# Equalizer_VUMeter.net
KiCad netlist of a schematic drawn in EAGLE
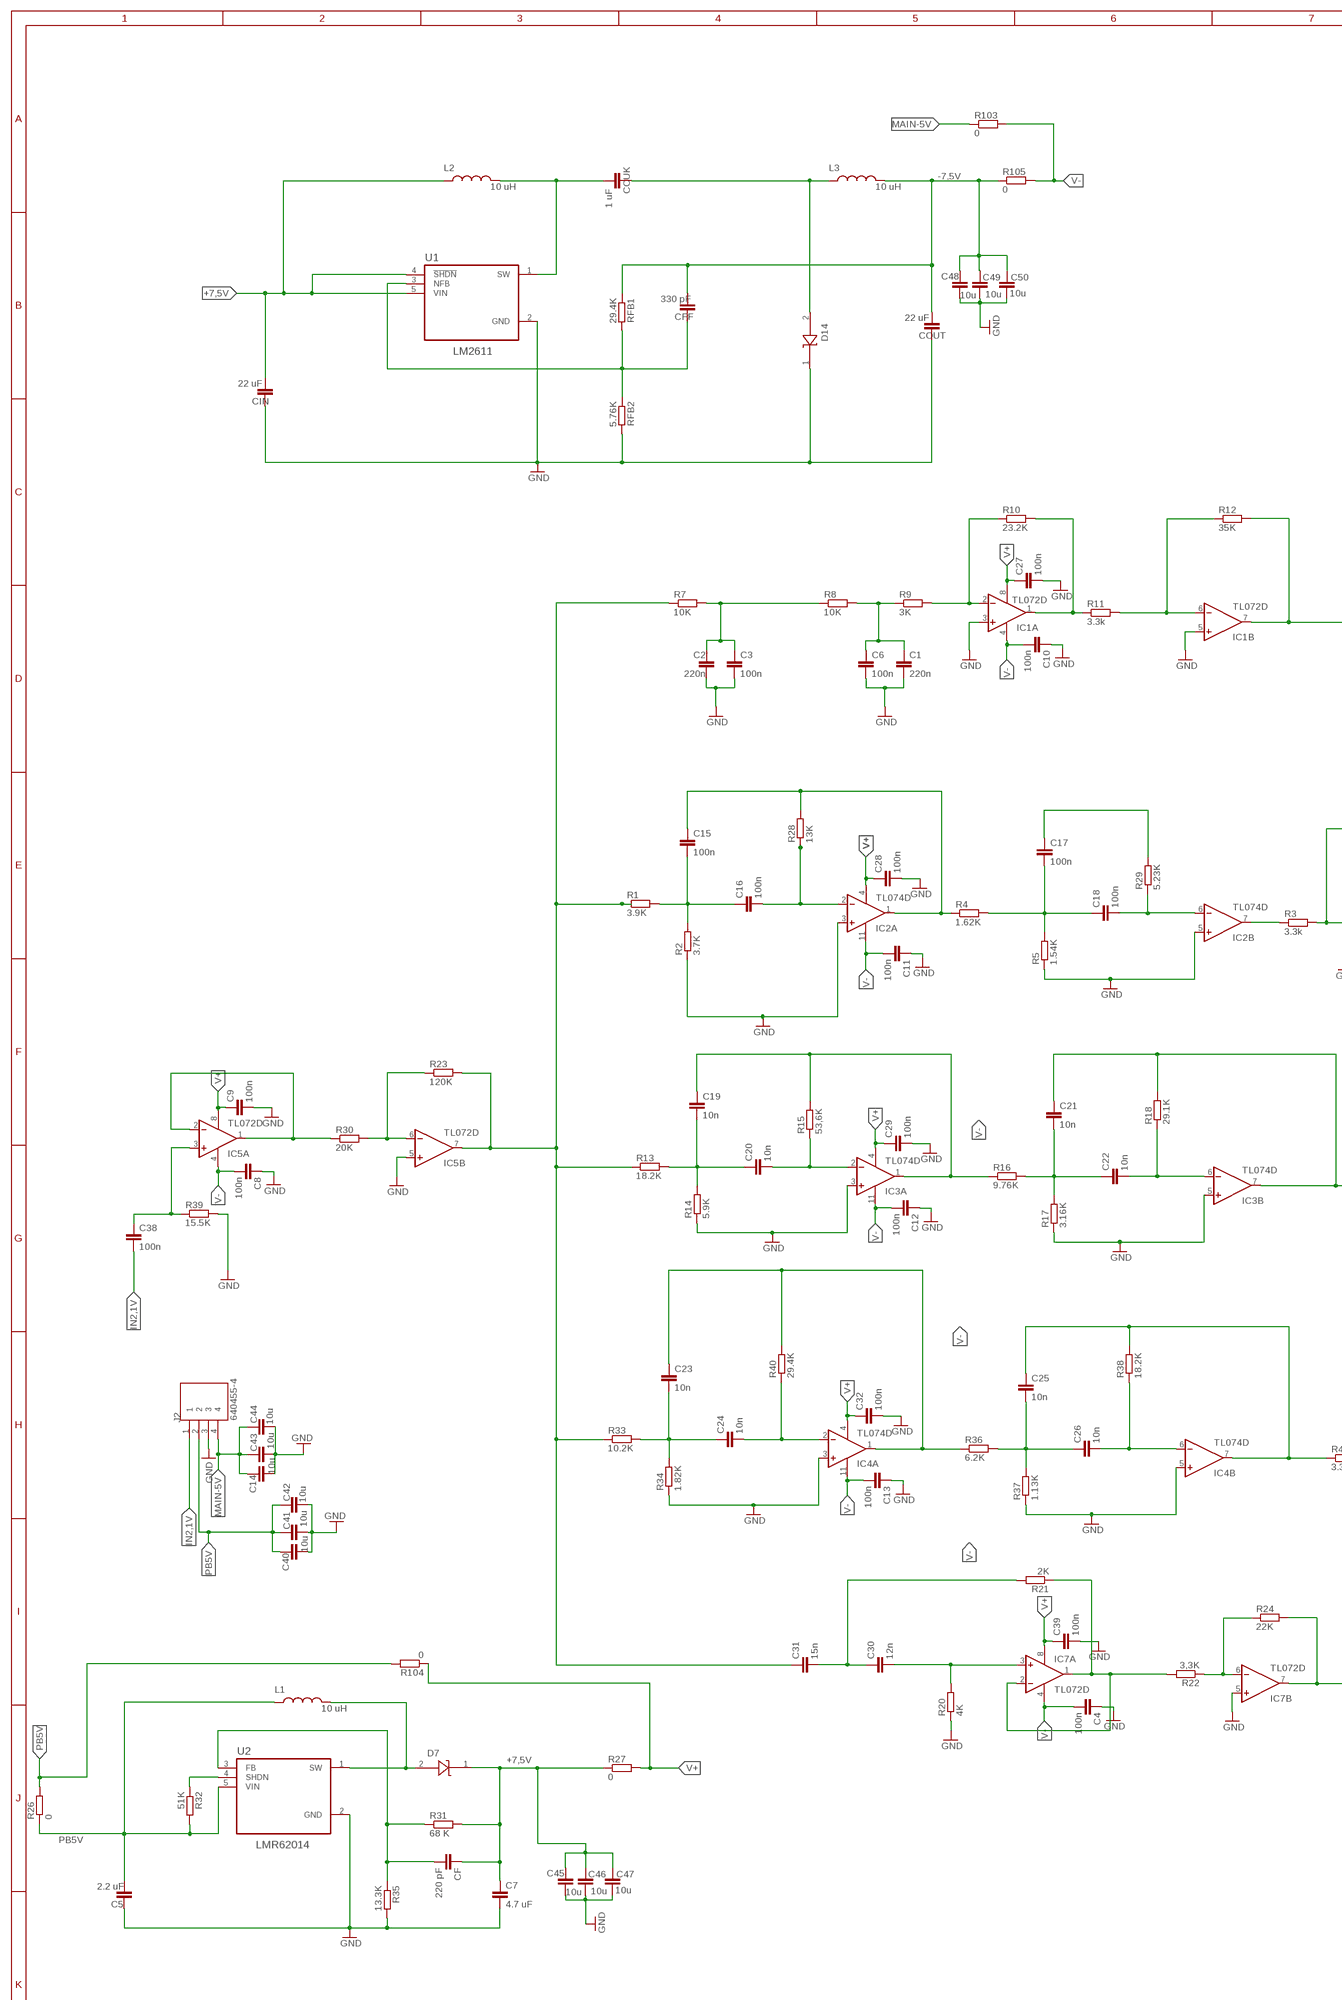
[diagram p0: schematic, sheet 1, part 1 of 3]
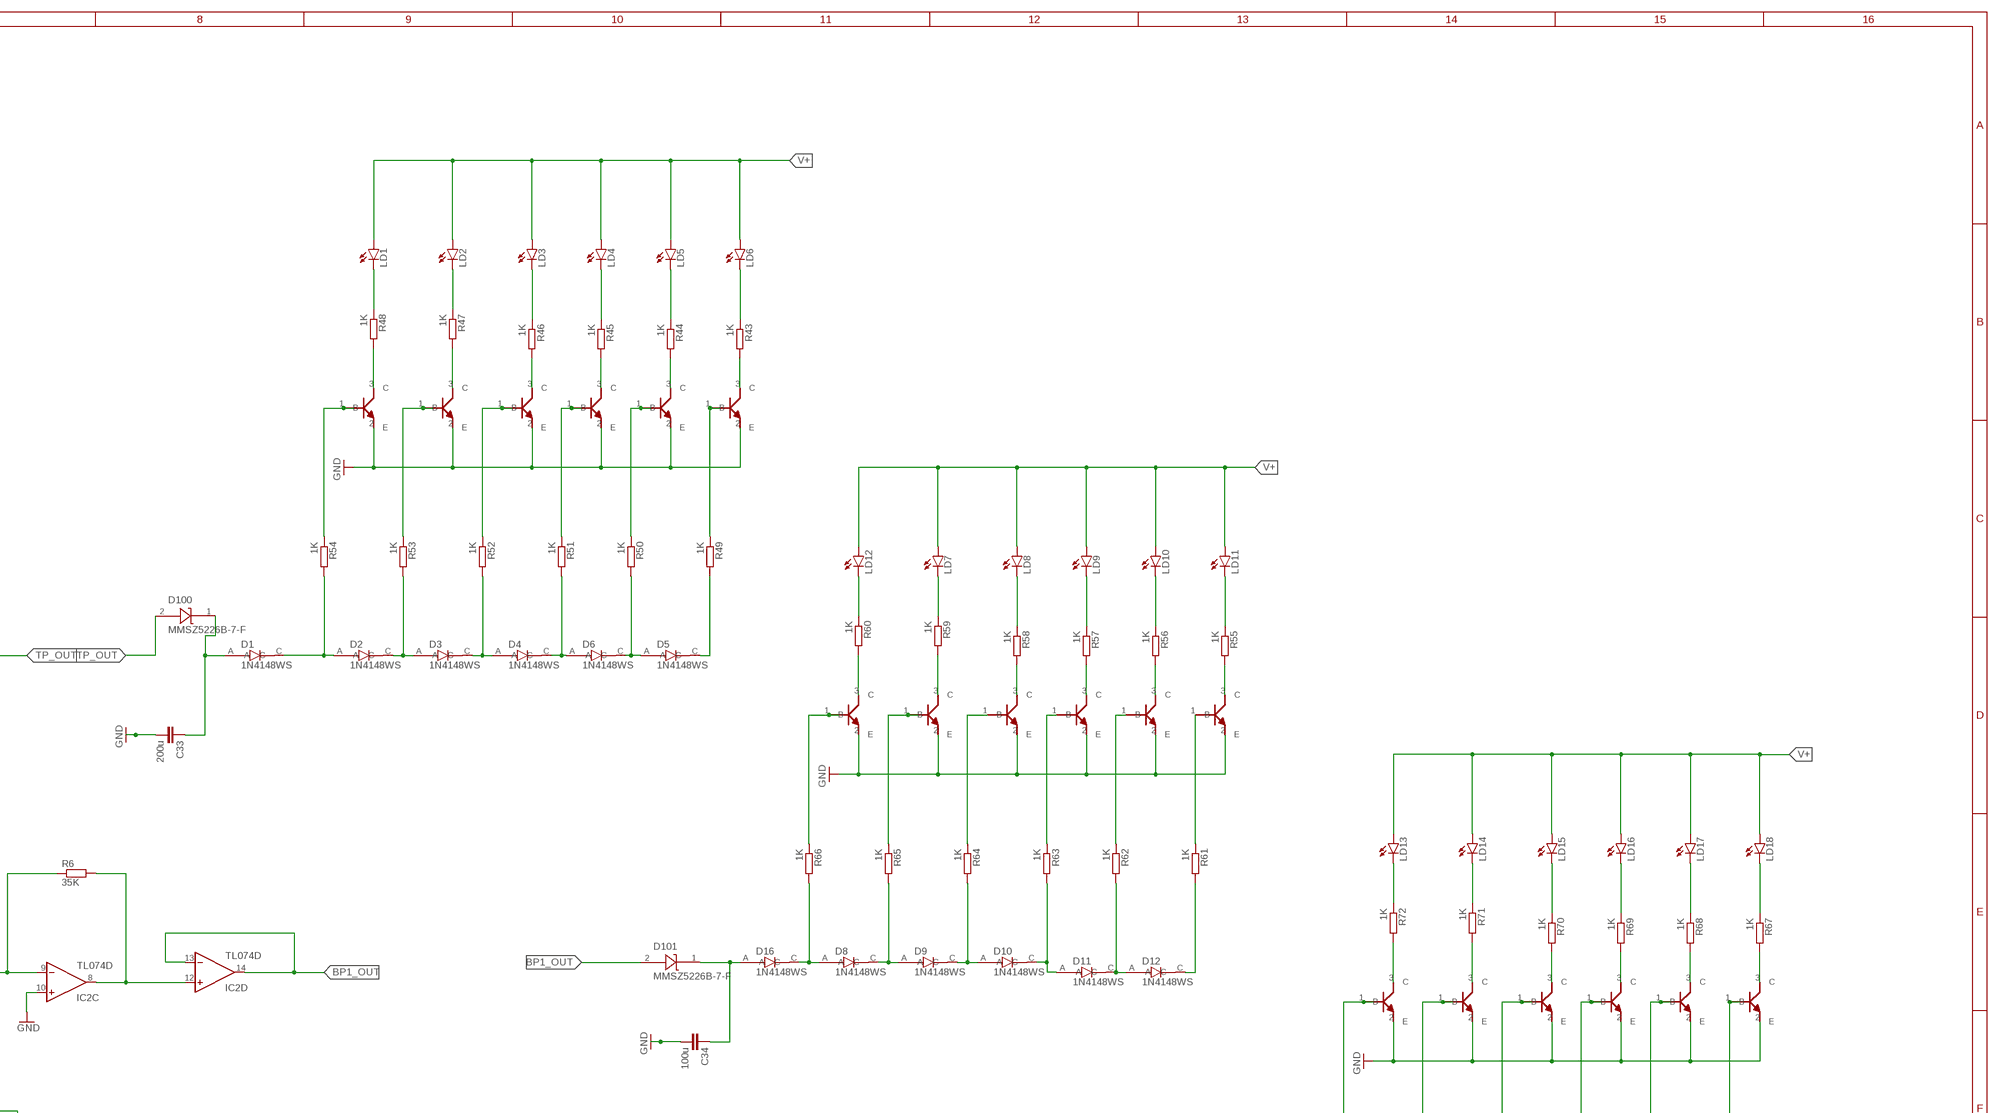
[diagram p1: schematic, sheet 1, part 2 of 3]
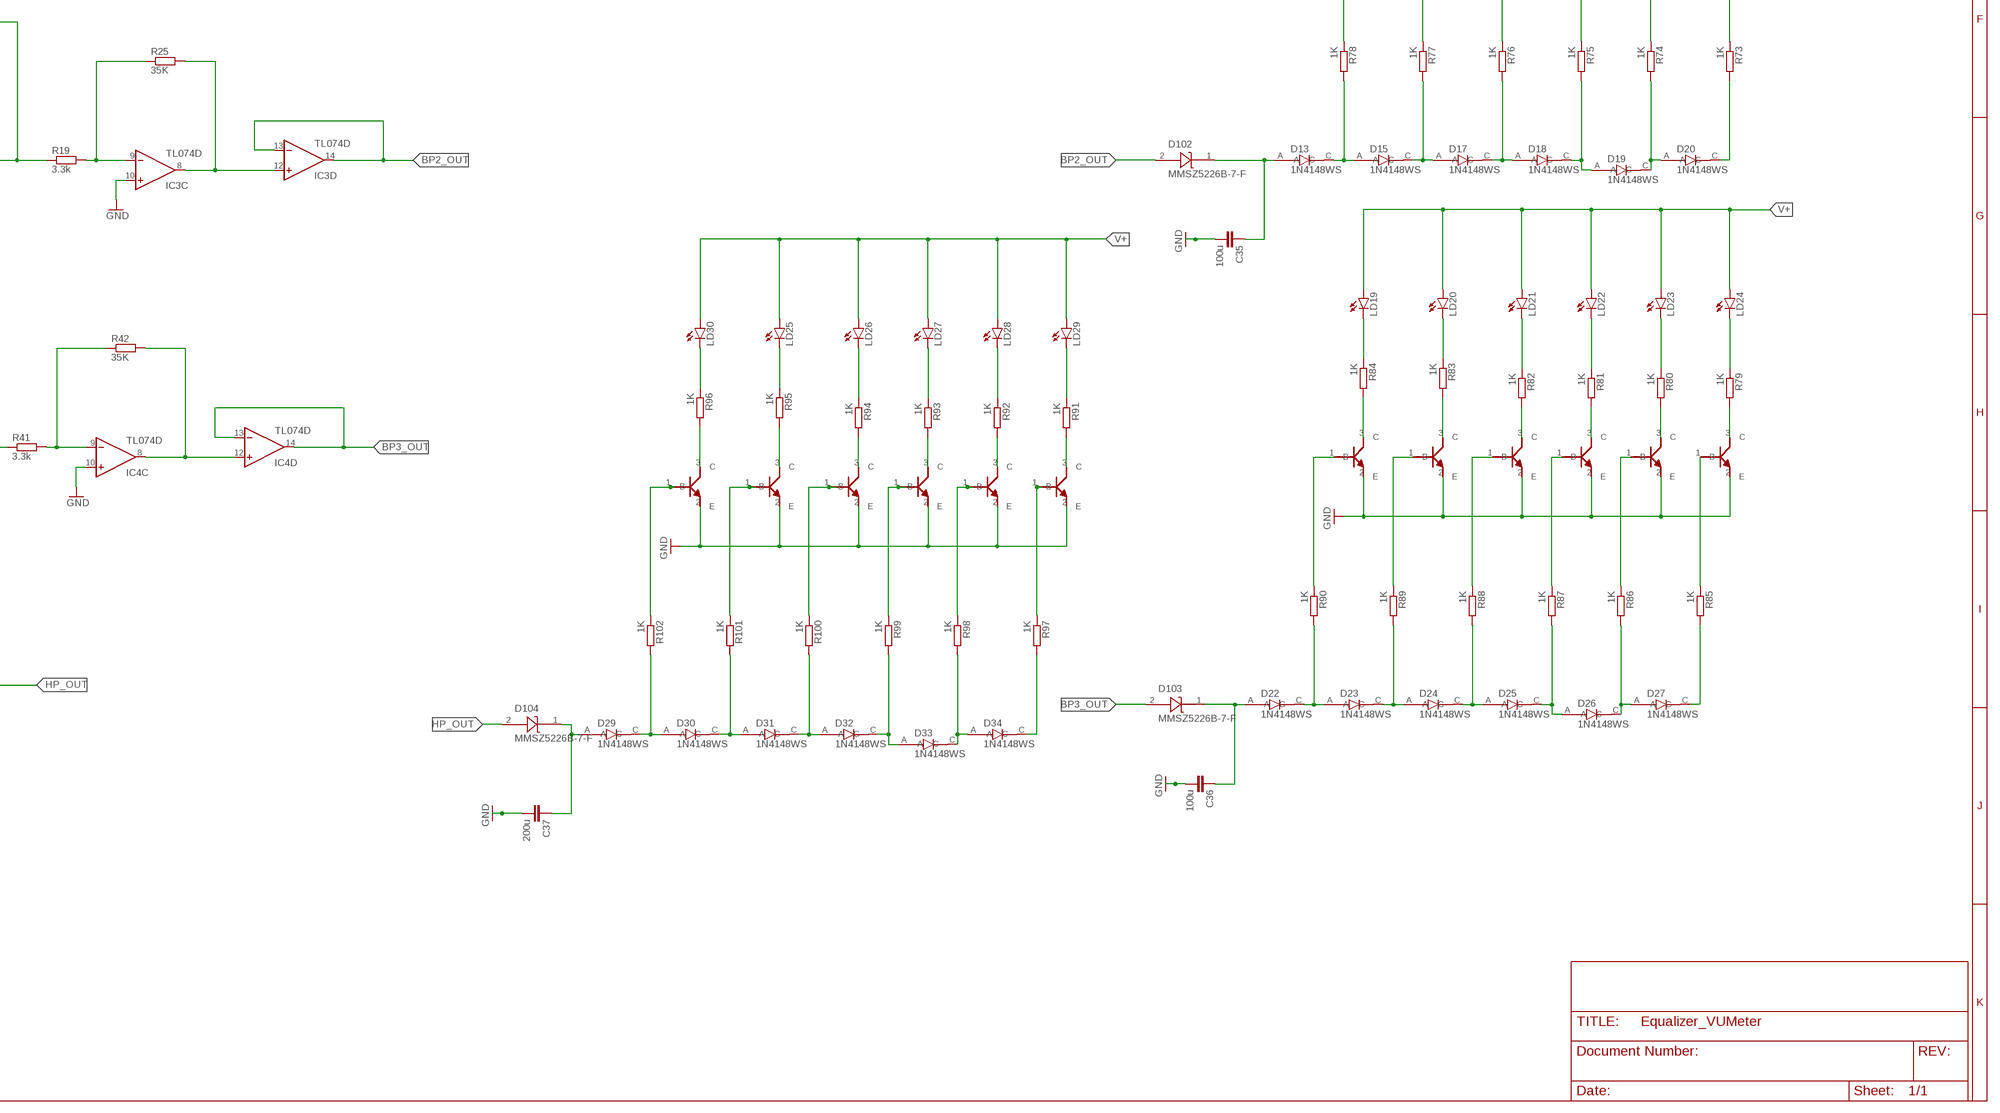
[diagram p2: schematic, sheet 1, part 3 of 3]

(export (version "E")
  (design (tool "Eeschema 10.0.6"))
  (components
    (comp (ref "C1")
      (value "220n")
      (footprint "eagle-import:C0603")
      (libsource (lib "eagle-import") (part "C-EUC0603"))
    )
    (comp (ref "C2")
      (value "220n")
      (footprint "eagle-import:C0603")
      (libsource (lib "eagle-import") (part "C-EUC0603"))
    )
    (comp (ref "C3")
      (value "100n")
      (footprint "eagle-import:C0603")
      (libsource (lib "eagle-import") (part "C-EUC0603"))
    )
    (comp (ref "C4")
      (value "100n")
      (footprint "eagle-import:C0603")
      (libsource (lib "eagle-import") (part "C-EUC0603"))
    )
    (comp (ref "C5")
      (value "2.2 uF")
      (footprint "eagle-import:C0603")
      (libsource (lib "eagle-import") (part "rcl_334_C-EUC0603"))
    )
    (comp (ref "C6")
      (value "100n")
      (footprint "eagle-import:C0603")
      (libsource (lib "eagle-import") (part "C-EUC0603"))
    )
    (comp (ref "C7")
      (value "4.7 uF")
      (footprint "eagle-import:C0603")
      (libsource (lib "eagle-import") (part "rcl_334_C-EUC0603"))
    )
    (comp (ref "C8")
      (value "100n")
      (footprint "eagle-import:C0603")
      (libsource (lib "eagle-import") (part "C-EUC0603"))
    )
    (comp (ref "C9")
      (value "100n")
      (footprint "eagle-import:C0603")
      (libsource (lib "eagle-import") (part "C-EUC0603"))
    )
    (comp (ref "C10")
      (value "100n")
      (footprint "eagle-import:C0603")
      (libsource (lib "eagle-import") (part "C-EUC0603"))
    )
    (comp (ref "C11")
      (value "100n")
      (footprint "eagle-import:C0603")
      (libsource (lib "eagle-import") (part "C-EUC0603"))
    )
    (comp (ref "C12")
      (value "100n")
      (footprint "eagle-import:C0603")
      (libsource (lib "eagle-import") (part "C-EUC0603"))
    )
    (comp (ref "C13")
      (value "100n")
      (footprint "eagle-import:C0603")
      (libsource (lib "eagle-import") (part "C-EUC0603"))
    )
    (comp (ref "C14")
      (value "10u")
      (footprint "eagle-import:C0603")
      (libsource (lib "eagle-import") (part "C-EUC0603"))
    )
    (comp (ref "C15")
      (value "100n")
      (footprint "eagle-import:C0603")
      (libsource (lib "eagle-import") (part "C-EUC0603"))
    )
    (comp (ref "C16")
      (value "100n")
      (footprint "eagle-import:C0603")
      (libsource (lib "eagle-import") (part "C-EUC0603"))
    )
    (comp (ref "C17")
      (value "100n")
      (footprint "eagle-import:C0603")
      (libsource (lib "eagle-import") (part "C-EUC0603"))
    )
    (comp (ref "C18")
      (value "100n")
      (footprint "eagle-import:C0603")
      (libsource (lib "eagle-import") (part "C-EUC0603"))
    )
    (comp (ref "C19")
      (value "10n")
      (footprint "eagle-import:C0603")
      (libsource (lib "eagle-import") (part "C-EUC0603"))
    )
    (comp (ref "C20")
      (value "10n")
      (footprint "eagle-import:C0603")
      (libsource (lib "eagle-import") (part "C-EUC0603"))
    )
    (comp (ref "C21")
      (value "10n")
      (footprint "eagle-import:C0603")
      (libsource (lib "eagle-import") (part "C-EUC0603"))
    )
    (comp (ref "C22")
      (value "10n")
      (footprint "eagle-import:C0603")
      (libsource (lib "eagle-import") (part "C-EUC0603"))
    )
    (comp (ref "C23")
      (value "10n")
      (footprint "eagle-import:C0603")
      (libsource (lib "eagle-import") (part "C-EUC0603"))
    )
    (comp (ref "C24")
      (value "10n")
      (footprint "eagle-import:C0603")
      (libsource (lib "eagle-import") (part "C-EUC0603"))
    )
    (comp (ref "C25")
      (value "10n")
      (footprint "eagle-import:C0603")
      (libsource (lib "eagle-import") (part "C-EUC0603"))
    )
    (comp (ref "C26")
      (value "10n")
      (footprint "eagle-import:C0603")
      (libsource (lib "eagle-import") (part "C-EUC0603"))
    )
    (comp (ref "C27")
      (value "100n")
      (footprint "eagle-import:C0603")
      (libsource (lib "eagle-import") (part "C-EUC0603"))
    )
    (comp (ref "C28")
      (value "100n")
      (footprint "eagle-import:C0603")
      (libsource (lib "eagle-import") (part "C-EUC0603"))
    )
    (comp (ref "C29")
      (value "100n")
      (footprint "eagle-import:C0603")
      (libsource (lib "eagle-import") (part "C-EUC0603"))
    )
    (comp (ref "C30")
      (value "12n")
      (footprint "eagle-import:C0603")
      (libsource (lib "eagle-import") (part "C-EUC0603"))
    )
    (comp (ref "C31")
      (value "15n")
      (footprint "eagle-import:C0603")
      (libsource (lib "eagle-import") (part "C-EUC0603"))
    )
    (comp (ref "C32")
      (value "100n")
      (footprint "eagle-import:C0603")
      (libsource (lib "eagle-import") (part "C-EUC0603"))
    )
    (comp (ref "C33")
      (value "200u")
      (footprint "eagle-import:C0603")
      (libsource (lib "eagle-import") (part "C-EUC0603"))
    )
    (comp (ref "C34")
      (value "100u")
      (footprint "eagle-import:C0603")
      (libsource (lib "eagle-import") (part "C-EUC0603"))
    )
    (comp (ref "C35")
      (value "100u")
      (footprint "eagle-import:C0603")
      (libsource (lib "eagle-import") (part "C-EUC0603"))
    )
    (comp (ref "C36")
      (value "100u")
      (footprint "eagle-import:C0603")
      (libsource (lib "eagle-import") (part "C-EUC0603"))
    )
    (comp (ref "C37")
      (value "200u")
      (footprint "eagle-import:C0603")
      (libsource (lib "eagle-import") (part "C-EUC0603"))
    )
    (comp (ref "C38")
      (value "100n")
      (footprint "eagle-import:C0603")
      (libsource (lib "eagle-import") (part "rcl_334_C-EUC0603"))
    )
    (comp (ref "C39")
      (value "100n")
      (footprint "eagle-import:C0603")
      (libsource (lib "eagle-import") (part "C-EUC0603"))
    )
    (comp (ref "C40")
      (value "10u")
      (footprint "eagle-import:C0603")
      (libsource (lib "eagle-import") (part "C-EUC0603"))
    )
    (comp (ref "C41")
      (value "10u")
      (footprint "eagle-import:C0603")
      (libsource (lib "eagle-import") (part "C-EUC0603"))
    )
    (comp (ref "C42")
      (value "10u")
      (footprint "eagle-import:C0603")
      (libsource (lib "eagle-import") (part "C-EUC0603"))
    )
    (comp (ref "C43")
      (value "10u")
      (footprint "eagle-import:C0603")
      (libsource (lib "eagle-import") (part "C-EUC0603"))
    )
    (comp (ref "C44")
      (value "10u")
      (footprint "eagle-import:C0603")
      (libsource (lib "eagle-import") (part "C-EUC0603"))
    )
    (comp (ref "C45")
      (value "10u")
      (footprint "eagle-import:C0603")
      (libsource (lib "eagle-import") (part "C-EUC0603"))
    )
    (comp (ref "C46")
      (value "10u")
      (footprint "eagle-import:C0603")
      (libsource (lib "eagle-import") (part "C-EUC0603"))
    )
    (comp (ref "C47")
      (value "10u")
      (footprint "eagle-import:C0603")
      (libsource (lib "eagle-import") (part "C-EUC0603"))
    )
    (comp (ref "C48")
      (value "10u")
      (footprint "eagle-import:C0603")
      (libsource (lib "eagle-import") (part "C-EUC0603"))
    )
    (comp (ref "C49")
      (value "10u")
      (footprint "eagle-import:C0603")
      (libsource (lib "eagle-import") (part "C-EUC0603"))
    )
    (comp (ref "C50")
      (value "10u")
      (footprint "eagle-import:C0603")
      (libsource (lib "eagle-import") (part "C-EUC0603"))
    )
    (comp (ref "CCUK")
      (value "1 uF")
      (footprint "eagle-import:C0603")
      (libsource (lib "eagle-import") (part "rcl_334_C-EUC0603"))
    )
    (comp (ref "CF")
      (value "220 pF")
      (footprint "eagle-import:C0603")
      (libsource (lib "eagle-import") (part "rcl_334_C-EUC0603"))
    )
    (comp (ref "CFF")
      (value "330 pF")
      (footprint "eagle-import:C0603")
      (libsource (lib "eagle-import") (part "rcl_334_C-EUC0603"))
    )
    (comp (ref "CIN")
      (value "22 uF")
      (footprint "eagle-import:C0603")
      (libsource (lib "eagle-import") (part "rcl_334_C-EUC0603"))
    )
    (comp (ref "COUT")
      (value "22 uF")
      (footprint "eagle-import:C0603")
      (libsource (lib "eagle-import") (part "rcl_334_C-EUC0603"))
    )
    (comp (ref "D1")
      (value "1N4148WS")
      (footprint "eagle-import:SODFL2512X100N")
      (fields (field (name "MF") "ON Semiconductor"))
      (libsource (lib "eagle-import") (part "1N4148WS"))
    )
    (comp (ref "D2")
      (value "1N4148WS")
      (footprint "eagle-import:SODFL2512X100N")
      (fields (field (name "MF") "ON Semiconductor"))
      (libsource (lib "eagle-import") (part "1N4148WS"))
    )
    (comp (ref "D3")
      (value "1N4148WS")
      (footprint "eagle-import:SODFL2512X100N")
      (fields (field (name "MF") "ON Semiconductor"))
      (libsource (lib "eagle-import") (part "1N4148WS"))
    )
    (comp (ref "D4")
      (value "1N4148WS")
      (footprint "eagle-import:SODFL2512X100N")
      (fields (field (name "MF") "ON Semiconductor"))
      (libsource (lib "eagle-import") (part "1N4148WS"))
    )
    (comp (ref "D5")
      (value "1N4148WS")
      (footprint "eagle-import:SODFL2512X100N")
      (fields (field (name "MF") "ON Semiconductor"))
      (libsource (lib "eagle-import") (part "1N4148WS"))
    )
    (comp (ref "D6")
      (value "1N4148WS")
      (footprint "eagle-import:SODFL2512X100N")
      (fields (field (name "MF") "ON Semiconductor"))
      (libsource (lib "eagle-import") (part "1N4148WS"))
    )
    (comp (ref "D7")
      (value "MMSZ5226B-7-F")
      (footprint "eagle-import:SOD3715X135L32X57N")
      (fields (field (name "MF") "Diodes Inc."))
      (libsource (lib "eagle-import") (part "MMSZ5226B-7-F"))
    )
    (comp (ref "D8")
      (value "1N4148WS")
      (footprint "eagle-import:SODFL2512X100N")
      (fields (field (name "MF") "ON Semiconductor"))
      (libsource (lib "eagle-import") (part "1N4148WS"))
    )
    (comp (ref "D9")
      (value "1N4148WS")
      (footprint "eagle-import:SODFL2512X100N")
      (fields (field (name "MF") "ON Semiconductor"))
      (libsource (lib "eagle-import") (part "1N4148WS"))
    )
    (comp (ref "D10")
      (value "1N4148WS")
      (footprint "eagle-import:SODFL2512X100N")
      (fields (field (name "MF") "ON Semiconductor"))
      (libsource (lib "eagle-import") (part "1N4148WS"))
    )
    (comp (ref "D11")
      (value "1N4148WS")
      (footprint "eagle-import:SODFL2512X100N")
      (fields (field (name "MF") "ON Semiconductor"))
      (libsource (lib "eagle-import") (part "1N4148WS"))
    )
    (comp (ref "D12")
      (value "1N4148WS")
      (footprint "eagle-import:SODFL2512X100N")
      (fields (field (name "MF") "ON Semiconductor"))
      (libsource (lib "eagle-import") (part "1N4148WS"))
    )
    (comp (ref "D13")
      (value "1N4148WS")
      (footprint "eagle-import:SODFL2512X100N")
      (fields (field (name "MF") "ON Semiconductor"))
      (libsource (lib "eagle-import") (part "1N4148WS"))
    )
    (comp (ref "D14")
      (value "MMSZ5226B-7-F")
      (footprint "eagle-import:SOD3715X135L32X57N")
      (fields (field (name "MF") "Diodes Inc."))
      (libsource (lib "eagle-import") (part "MMSZ5226B-7-F"))
    )
    (comp (ref "D15")
      (value "1N4148WS")
      (footprint "eagle-import:SODFL2512X100N")
      (fields (field (name "MF") "ON Semiconductor"))
      (libsource (lib "eagle-import") (part "1N4148WS"))
    )
    (comp (ref "D16")
      (value "1N4148WS")
      (footprint "eagle-import:SODFL2512X100N")
      (fields (field (name "MF") "ON Semiconductor"))
      (libsource (lib "eagle-import") (part "1N4148WS"))
    )
    (comp (ref "D17")
      (value "1N4148WS")
      (footprint "eagle-import:SODFL2512X100N")
      (fields (field (name "MF") "ON Semiconductor"))
      (libsource (lib "eagle-import") (part "1N4148WS"))
    )
    (comp (ref "D18")
      (value "1N4148WS")
      (footprint "eagle-import:SODFL2512X100N")
      (fields (field (name "MF") "ON Semiconductor"))
      (libsource (lib "eagle-import") (part "1N4148WS"))
    )
    (comp (ref "D19")
      (value "1N4148WS")
      (footprint "eagle-import:SODFL2512X100N")
      (fields (field (name "MF") "ON Semiconductor"))
      (libsource (lib "eagle-import") (part "1N4148WS"))
    )
    (comp (ref "D20")
      (value "1N4148WS")
      (footprint "eagle-import:SODFL2512X100N")
      (fields (field (name "MF") "ON Semiconductor"))
      (libsource (lib "eagle-import") (part "1N4148WS"))
    )
    (comp (ref "D22")
      (value "1N4148WS")
      (footprint "eagle-import:SODFL2512X100N")
      (fields (field (name "MF") "ON Semiconductor"))
      (libsource (lib "eagle-import") (part "1N4148WS"))
    )
    (comp (ref "D23")
      (value "1N4148WS")
      (footprint "eagle-import:SODFL2512X100N")
      (fields (field (name "MF") "ON Semiconductor"))
      (libsource (lib "eagle-import") (part "1N4148WS"))
    )
    (comp (ref "D24")
      (value "1N4148WS")
      (footprint "eagle-import:SODFL2512X100N")
      (fields (field (name "MF") "ON Semiconductor"))
      (libsource (lib "eagle-import") (part "1N4148WS"))
    )
    (comp (ref "D25")
      (value "1N4148WS")
      (footprint "eagle-import:SODFL2512X100N")
      (fields (field (name "MF") "ON Semiconductor"))
      (libsource (lib "eagle-import") (part "1N4148WS"))
    )
    (comp (ref "D26")
      (value "1N4148WS")
      (footprint "eagle-import:SODFL2512X100N")
      (fields (field (name "MF") "ON Semiconductor"))
      (libsource (lib "eagle-import") (part "1N4148WS"))
    )
    (comp (ref "D27")
      (value "1N4148WS")
      (footprint "eagle-import:SODFL2512X100N")
      (fields (field (name "MF") "ON Semiconductor"))
      (libsource (lib "eagle-import") (part "1N4148WS"))
    )
    (comp (ref "D29")
      (value "1N4148WS")
      (footprint "eagle-import:SODFL2512X100N")
      (fields (field (name "MF") "ON Semiconductor"))
      (libsource (lib "eagle-import") (part "1N4148WS"))
    )
    (comp (ref "D30")
      (value "1N4148WS")
      (footprint "eagle-import:SODFL2512X100N")
      (fields (field (name "MF") "ON Semiconductor"))
      (libsource (lib "eagle-import") (part "1N4148WS"))
    )
    (comp (ref "D31")
      (value "1N4148WS")
      (footprint "eagle-import:SODFL2512X100N")
      (fields (field (name "MF") "ON Semiconductor"))
      (libsource (lib "eagle-import") (part "1N4148WS"))
    )
    (comp (ref "D32")
      (value "1N4148WS")
      (footprint "eagle-import:SODFL2512X100N")
      (fields (field (name "MF") "ON Semiconductor"))
      (libsource (lib "eagle-import") (part "1N4148WS"))
    )
    (comp (ref "D33")
      (value "1N4148WS")
      (footprint "eagle-import:SODFL2512X100N")
      (fields (field (name "MF") "ON Semiconductor"))
      (libsource (lib "eagle-import") (part "1N4148WS"))
    )
    (comp (ref "D34")
      (value "1N4148WS")
      (footprint "eagle-import:SODFL2512X100N")
      (fields (field (name "MF") "ON Semiconductor"))
      (libsource (lib "eagle-import") (part "1N4148WS"))
    )
    (comp (ref "D100")
      (value "MMSZ5226B-7-F")
      (footprint "eagle-import:SOD3715X135L32X57N")
      (fields (field (name "MF") "Diodes Inc."))
      (libsource (lib "eagle-import") (part "MMSZ5226B-7-F"))
    )
    (comp (ref "D101")
      (value "MMSZ5226B-7-F")
      (footprint "eagle-import:SOD3715X135L32X57N")
      (fields (field (name "MF") "Diodes Inc."))
      (libsource (lib "eagle-import") (part "MMSZ5226B-7-F"))
    )
    (comp (ref "D102")
      (value "MMSZ5226B-7-F")
      (footprint "eagle-import:SOD3715X135L32X57N")
      (fields (field (name "MF") "Diodes Inc."))
      (libsource (lib "eagle-import") (part "MMSZ5226B-7-F"))
    )
    (comp (ref "D103")
      (value "MMSZ5226B-7-F")
      (footprint "eagle-import:SOD3715X135L32X57N")
      (fields (field (name "MF") "Diodes Inc."))
      (libsource (lib "eagle-import") (part "MMSZ5226B-7-F"))
    )
    (comp (ref "D104")
      (value "MMSZ5226B-7-F")
      (footprint "eagle-import:SOD3715X135L32X57N")
      (fields (field (name "MF") "Diodes Inc."))
      (libsource (lib "eagle-import") (part "MMSZ5226B-7-F"))
    )
    (comp (ref "IC1")
      (value "TL072D")
      (footprint "eagle-import:SO08")
      (libsource (lib "eagle-import") (part "TL072D"))
    )
    (comp (ref "IC2")
      (value "TL074D")
      (footprint "eagle-import:SO14")
      (libsource (lib "eagle-import") (part "TL074D"))
    )
    (comp (ref "IC3")
      (value "TL074D")
      (footprint "eagle-import:SO14")
      (libsource (lib "eagle-import") (part "TL074D"))
    )
    (comp (ref "IC4")
      (value "TL074D")
      (footprint "eagle-import:SO14")
      (libsource (lib "eagle-import") (part "TL074D"))
    )
    (comp (ref "IC5")
      (value "TL072D")
      (footprint "eagle-import:SO08")
      (libsource (lib "eagle-import") (part "TL072D"))
    )
    (comp (ref "IC7")
      (value "TL072D")
      (footprint "eagle-import:SO08")
      (libsource (lib "eagle-import") (part "TL072D"))
    )
    (comp (ref "J2")
      (value "640455-4")
      (footprint "eagle-import:TE_640455-4")
      (fields (field (name "MF") "TE Connectivity"))
      (libsource (lib "eagle-import") (part "640455-4"))
    )
    (comp (ref "L1")
      (value "10 uH")
      (footprint "eagle-import:INDC1608X95N")
      (fields (field (name "MF") "Abracon LLC") (field (name "MP") "ASMCI-0603-100M-T"))
      (libsource (lib "eagle-import") (part "ASMCI-0603-100M-T"))
    )
    (comp (ref "L2")
      (value "10 uH")
      (footprint "eagle-import:INDC1608X95N")
      (fields (field (name "MF") "Abracon LLC") (field (name "MP") "ASMCI-0603-100M-T"))
      (libsource (lib "eagle-import") (part "ASMCI-0603-100M-T"))
    )
    (comp (ref "L3")
      (value "10 uH")
      (footprint "eagle-import:INDC1608X95N")
      (fields (field (name "MF") "Abracon LLC") (field (name "MP") "ASMCI-0603-100M-T"))
      (libsource (lib "eagle-import") (part "ASMCI-0603-100M-T"))
    )
    (comp (ref "LD1")
      (value "LEDCHIP-LED0603")
      (footprint "eagle-import:CHIP-LED0603")
      (libsource (lib "eagle-import") (part "LEDCHIP-LED0603"))
    )
    (comp (ref "LD2")
      (value "LEDCHIP-LED0603")
      (footprint "eagle-import:CHIP-LED0603")
      (libsource (lib "eagle-import") (part "LEDCHIP-LED0603"))
    )
    (comp (ref "LD3")
      (value "LEDCHIP-LED0603")
      (footprint "eagle-import:CHIP-LED0603")
      (libsource (lib "eagle-import") (part "LEDCHIP-LED0603"))
    )
    (comp (ref "LD4")
      (value "LEDCHIP-LED0603")
      (footprint "eagle-import:CHIP-LED0603")
      (libsource (lib "eagle-import") (part "LEDCHIP-LED0603"))
    )
    (comp (ref "LD5")
      (value "LEDCHIP-LED0603")
      (footprint "eagle-import:CHIP-LED0603")
      (libsource (lib "eagle-import") (part "LEDCHIP-LED0603"))
    )
    (comp (ref "LD6")
      (value "LEDCHIP-LED0603")
      (footprint "eagle-import:CHIP-LED0603")
      (libsource (lib "eagle-import") (part "LEDCHIP-LED0603"))
    )
    (comp (ref "LD7")
      (value "LEDCHIP-LED0603")
      (footprint "eagle-import:CHIP-LED0603")
      (libsource (lib "eagle-import") (part "LEDCHIP-LED0603"))
    )
    (comp (ref "LD8")
      (value "LEDCHIP-LED0603")
      (footprint "eagle-import:CHIP-LED0603")
      (libsource (lib "eagle-import") (part "LEDCHIP-LED0603"))
    )
    (comp (ref "LD9")
      (value "LEDCHIP-LED0603")
      (footprint "eagle-import:CHIP-LED0603")
      (libsource (lib "eagle-import") (part "LEDCHIP-LED0603"))
    )
    (comp (ref "LD10")
      (value "LEDCHIP-LED0603")
      (footprint "eagle-import:CHIP-LED0603")
      (libsource (lib "eagle-import") (part "LEDCHIP-LED0603"))
    )
    (comp (ref "LD11")
      (value "LEDCHIP-LED0603")
      (footprint "eagle-import:CHIP-LED0603")
      (libsource (lib "eagle-import") (part "LEDCHIP-LED0603"))
    )
    (comp (ref "LD12")
      (value "LEDCHIP-LED0603")
      (footprint "eagle-import:CHIP-LED0603")
      (libsource (lib "eagle-import") (part "LEDCHIP-LED0603"))
    )
    (comp (ref "LD13")
      (value "LEDCHIP-LED0603")
      (footprint "eagle-import:CHIP-LED0603")
      (libsource (lib "eagle-import") (part "LEDCHIP-LED0603"))
    )
    (comp (ref "LD14")
      (value "LEDCHIP-LED0603")
      (footprint "eagle-import:CHIP-LED0603")
      (libsource (lib "eagle-import") (part "LEDCHIP-LED0603"))
    )
    (comp (ref "LD15")
      (value "LEDCHIP-LED0603")
      (footprint "eagle-import:CHIP-LED0603")
      (libsource (lib "eagle-import") (part "LEDCHIP-LED0603"))
    )
    (comp (ref "LD16")
      (value "LEDCHIP-LED0603")
      (footprint "eagle-import:CHIP-LED0603")
      (libsource (lib "eagle-import") (part "LEDCHIP-LED0603"))
    )
    (comp (ref "LD17")
      (value "LEDCHIP-LED0603")
      (footprint "eagle-import:CHIP-LED0603")
      (libsource (lib "eagle-import") (part "LEDCHIP-LED0603"))
    )
    (comp (ref "LD18")
      (value "LEDCHIP-LED0603")
      (footprint "eagle-import:CHIP-LED0603")
      (libsource (lib "eagle-import") (part "LEDCHIP-LED0603"))
    )
    (comp (ref "LD19")
      (value "LEDCHIP-LED0603")
      (footprint "eagle-import:CHIP-LED0603")
      (libsource (lib "eagle-import") (part "LEDCHIP-LED0603"))
    )
    (comp (ref "LD20")
      (value "LEDCHIP-LED0603")
      (footprint "eagle-import:CHIP-LED0603")
      (libsource (lib "eagle-import") (part "LEDCHIP-LED0603"))
    )
    (comp (ref "LD21")
      (value "LEDCHIP-LED0603")
      (footprint "eagle-import:CHIP-LED0603")
      (libsource (lib "eagle-import") (part "LEDCHIP-LED0603"))
    )
    (comp (ref "LD22")
      (value "LEDCHIP-LED0603")
      (footprint "eagle-import:CHIP-LED0603")
      (libsource (lib "eagle-import") (part "LEDCHIP-LED0603"))
    )
    (comp (ref "LD23")
      (value "LEDCHIP-LED0603")
      (footprint "eagle-import:CHIP-LED0603")
      (libsource (lib "eagle-import") (part "LEDCHIP-LED0603"))
    )
    (comp (ref "LD24")
      (value "LEDCHIP-LED0603")
      (footprint "eagle-import:CHIP-LED0603")
      (libsource (lib "eagle-import") (part "LEDCHIP-LED0603"))
    )
    (comp (ref "LD25")
      (value "LEDCHIP-LED0603")
      (footprint "eagle-import:CHIP-LED0603")
      (libsource (lib "eagle-import") (part "LEDCHIP-LED0603"))
    )
    (comp (ref "LD26")
      (value "LEDCHIP-LED0603")
      (footprint "eagle-import:CHIP-LED0603")
      (libsource (lib "eagle-import") (part "LEDCHIP-LED0603"))
    )
    (comp (ref "LD27")
      (value "LEDCHIP-LED0603")
      (footprint "eagle-import:CHIP-LED0603")
      (libsource (lib "eagle-import") (part "LEDCHIP-LED0603"))
    )
    (comp (ref "LD28")
      (value "LEDCHIP-LED0603")
      (footprint "eagle-import:CHIP-LED0603")
      (libsource (lib "eagle-import") (part "LEDCHIP-LED0603"))
    )
    (comp (ref "LD29")
      (value "LEDCHIP-LED0603")
      (footprint "eagle-import:CHIP-LED0603")
      (libsource (lib "eagle-import") (part "LEDCHIP-LED0603"))
    )
    (comp (ref "LD30")
      (value "LEDCHIP-LED0603")
      (footprint "eagle-import:CHIP-LED0603")
      (libsource (lib "eagle-import") (part "LEDCHIP-LED0603"))
    )
    (comp (ref "R1")
      (value "3.9K")
      (footprint "eagle-import:R0603")
      (libsource (lib "eagle-import") (part "R-EU_R0603"))
    )
    (comp (ref "R2")
      (value "3.7K")
      (footprint "eagle-import:R0603")
      (libsource (lib "eagle-import") (part "R-EU_R0603"))
    )
    (comp (ref "R3")
      (value "3.3k")
      (footprint "eagle-import:R0603")
      (libsource (lib "eagle-import") (part "R-EU_R0603"))
    )
    (comp (ref "R4")
      (value "1.62K")
      (footprint "eagle-import:R0603")
      (libsource (lib "eagle-import") (part "R-EU_R0603"))
    )
    (comp (ref "R5")
      (value "1.54K")
      (footprint "eagle-import:R0603")
      (libsource (lib "eagle-import") (part "R-EU_R0603"))
    )
    (comp (ref "R6")
      (value "35K")
      (footprint "eagle-import:R0603")
      (libsource (lib "eagle-import") (part "R-EU_R0603"))
    )
    (comp (ref "R7")
      (value "10K")
      (footprint "eagle-import:R0603")
      (libsource (lib "eagle-import") (part "R-EU_R0603"))
    )
    (comp (ref "R8")
      (value "10K")
      (footprint "eagle-import:R0603")
      (libsource (lib "eagle-import") (part "R-EU_R0603"))
    )
    (comp (ref "R9")
      (value "3K")
      (footprint "eagle-import:R0603")
      (libsource (lib "eagle-import") (part "R-EU_R0603"))
    )
    (comp (ref "R10")
      (value "23.2K")
      (footprint "eagle-import:R0603")
      (libsource (lib "eagle-import") (part "R-EU_R0603"))
    )
    (comp (ref "R11")
      (value "3.3k")
      (footprint "eagle-import:R0603")
      (libsource (lib "eagle-import") (part "R-EU_R0603"))
    )
    (comp (ref "R12")
      (value "35K")
      (footprint "eagle-import:R0603")
      (libsource (lib "eagle-import") (part "R-EU_R0603"))
    )
    (comp (ref "R13")
      (value "18.2K")
      (footprint "eagle-import:R0603")
      (libsource (lib "eagle-import") (part "R-EU_R0603"))
    )
    (comp (ref "R14")
      (value "5.9K")
      (footprint "eagle-import:R0603")
      (libsource (lib "eagle-import") (part "R-EU_R0603"))
    )
    (comp (ref "R15")
      (value "53,6K")
      (footprint "eagle-import:R0603")
      (libsource (lib "eagle-import") (part "R-EU_R0603"))
    )
    (comp (ref "R16")
      (value "9.76K")
      (footprint "eagle-import:R0603")
      (libsource (lib "eagle-import") (part "R-EU_R0603"))
    )
    (comp (ref "R17")
      (value "3.16K")
      (footprint "eagle-import:R0603")
      (libsource (lib "eagle-import") (part "R-EU_R0603"))
    )
    (comp (ref "R18")
      (value "29.1K")
      (footprint "eagle-import:R0603")
      (libsource (lib "eagle-import") (part "R-EU_R0603"))
    )
    (comp (ref "R19")
      (value "3.3k")
      (footprint "eagle-import:R0603")
      (libsource (lib "eagle-import") (part "R-EU_R0603"))
    )
    (comp (ref "R20")
      (value "4K")
      (footprint "eagle-import:R0603")
      (libsource (lib "eagle-import") (part "R-EU_R0603"))
    )
    (comp (ref "R21")
      (value "2K")
      (footprint "eagle-import:R0603")
      (libsource (lib "eagle-import") (part "R-EU_R0603"))
    )
    (comp (ref "R22")
      (value "3,3K")
      (footprint "eagle-import:R0603")
      (libsource (lib "eagle-import") (part "R-EU_R0603"))
    )
    (comp (ref "R23")
      (value "120K")
      (footprint "eagle-import:R0603")
      (libsource (lib "eagle-import") (part "R-EU_R0603"))
    )
    (comp (ref "R24")
      (value "22K")
      (footprint "eagle-import:R0603")
      (libsource (lib "eagle-import") (part "R-EU_R0603"))
    )
    (comp (ref "R25")
      (value "35K")
      (footprint "eagle-import:R0603")
      (libsource (lib "eagle-import") (part "R-EU_R0603"))
    )
    (comp (ref "R26")
      (value "0")
      (footprint "eagle-import:R0603")
      (libsource (lib "eagle-import") (part "R-EU_R0603"))
    )
    (comp (ref "R27")
      (value "0")
      (footprint "eagle-import:R0603")
      (libsource (lib "eagle-import") (part "R-EU_R0603"))
    )
    (comp (ref "R28")
      (value "13K")
      (footprint "eagle-import:R0603")
      (libsource (lib "eagle-import") (part "R-EU_R0603"))
    )
    (comp (ref "R29")
      (value "5.23K")
      (footprint "eagle-import:R0603")
      (libsource (lib "eagle-import") (part "R-EU_R0603"))
    )
    (comp (ref "R30")
      (value "20K")
      (footprint "eagle-import:R0603")
      (libsource (lib "eagle-import") (part "R-EU_R0603"))
    )
    (comp (ref "R31")
      (value "68 K")
      (footprint "eagle-import:R0603")
      (libsource (lib "eagle-import") (part "R-EU_R0603"))
    )
    (comp (ref "R32")
      (value "51K")
      (footprint "eagle-import:R0603")
      (libsource (lib "eagle-import") (part "R-EU_R0603"))
    )
    (comp (ref "R33")
      (value "10.2K")
      (footprint "eagle-import:R0603")
      (libsource (lib "eagle-import") (part "R-EU_R0603"))
    )
    (comp (ref "R34")
      (value "1.82K")
      (footprint "eagle-import:R0603")
      (libsource (lib "eagle-import") (part "R-EU_R0603"))
    )
    (comp (ref "R35")
      (value "13.3K")
      (footprint "eagle-import:R0603")
      (libsource (lib "eagle-import") (part "R-EU_R0603"))
    )
    (comp (ref "R36")
      (value "6.2K")
      (footprint "eagle-import:R0603")
      (libsource (lib "eagle-import") (part "R-EU_R0603"))
    )
    (comp (ref "R37")
      (value "1.13K")
      (footprint "eagle-import:R0603")
      (libsource (lib "eagle-import") (part "R-EU_R0603"))
    )
    (comp (ref "R38")
      (value "18.2K")
      (footprint "eagle-import:R0603")
      (libsource (lib "eagle-import") (part "R-EU_R0603"))
    )
    (comp (ref "R39")
      (value "15.5K")
      (footprint "eagle-import:R0603")
      (libsource (lib "eagle-import") (part "R-EU_R0603"))
    )
    (comp (ref "R40")
      (value "29.4K")
      (footprint "eagle-import:R0603")
      (libsource (lib "eagle-import") (part "R-EU_R0603"))
    )
    (comp (ref "R41")
      (value "3.3k")
      (footprint "eagle-import:R0603")
      (libsource (lib "eagle-import") (part "R-EU_R0603"))
    )
    (comp (ref "R42")
      (value "35K")
      (footprint "eagle-import:R0603")
      (libsource (lib "eagle-import") (part "R-EU_R0603"))
    )
    (comp (ref "R43")
      (value "1K")
      (footprint "eagle-import:R0603")
      (libsource (lib "eagle-import") (part "R-EU_R0603"))
    )
    (comp (ref "R44")
      (value "1K")
      (footprint "eagle-import:R0603")
      (libsource (lib "eagle-import") (part "R-EU_R0603"))
    )
    (comp (ref "R45")
      (value "1K")
      (footprint "eagle-import:R0603")
      (libsource (lib "eagle-import") (part "R-EU_R0603"))
    )
    (comp (ref "R46")
      (value "1K")
      (footprint "eagle-import:R0603")
      (libsource (lib "eagle-import") (part "R-EU_R0603"))
    )
    (comp (ref "R47")
      (value "1K")
      (footprint "eagle-import:R0603")
      (libsource (lib "eagle-import") (part "R-EU_R0603"))
    )
    (comp (ref "R48")
      (value "1K")
      (footprint "eagle-import:R0603")
      (libsource (lib "eagle-import") (part "R-EU_R0603"))
    )
    (comp (ref "R49")
      (value "1K")
      (footprint "eagle-import:R0603")
      (libsource (lib "eagle-import") (part "R-EU_R0603"))
    )
    (comp (ref "R50")
      (value "1K")
      (footprint "eagle-import:R0603")
      (libsource (lib "eagle-import") (part "R-EU_R0603"))
    )
    (comp (ref "R51")
      (value "1K")
      (footprint "eagle-import:R0603")
      (libsource (lib "eagle-import") (part "R-EU_R0603"))
    )
    (comp (ref "R52")
      (value "1K")
      (footprint "eagle-import:R0603")
      (libsource (lib "eagle-import") (part "R-EU_R0603"))
    )
    (comp (ref "R53")
      (value "1K")
      (footprint "eagle-import:R0603")
      (libsource (lib "eagle-import") (part "R-EU_R0603"))
    )
    (comp (ref "R54")
      (value "1K")
      (footprint "eagle-import:R0603")
      (libsource (lib "eagle-import") (part "R-EU_R0603"))
    )
    (comp (ref "R55")
      (value "1K")
      (footprint "eagle-import:R0603")
      (libsource (lib "eagle-import") (part "R-EU_R0603"))
    )
    (comp (ref "R56")
      (value "1K")
      (footprint "eagle-import:R0603")
      (libsource (lib "eagle-import") (part "R-EU_R0603"))
    )
    (comp (ref "R57")
      (value "1K")
      (footprint "eagle-import:R0603")
      (libsource (lib "eagle-import") (part "R-EU_R0603"))
    )
    (comp (ref "R58")
      (value "1K")
      (footprint "eagle-import:R0603")
      (libsource (lib "eagle-import") (part "R-EU_R0603"))
    )
    (comp (ref "R59")
      (value "1K")
      (footprint "eagle-import:R0603")
      (libsource (lib "eagle-import") (part "R-EU_R0603"))
    )
    (comp (ref "R60")
      (value "1K")
      (footprint "eagle-import:R0603")
      (libsource (lib "eagle-import") (part "R-EU_R0603"))
    )
    (comp (ref "R61")
      (value "1K")
      (footprint "eagle-import:R0603")
      (libsource (lib "eagle-import") (part "R-EU_R0603"))
    )
    (comp (ref "R62")
      (value "1K")
      (footprint "eagle-import:R0603")
      (libsource (lib "eagle-import") (part "R-EU_R0603"))
    )
    (comp (ref "R63")
      (value "1K")
      (footprint "eagle-import:R0603")
      (libsource (lib "eagle-import") (part "R-EU_R0603"))
    )
    (comp (ref "R64")
      (value "1K")
      (footprint "eagle-import:R0603")
      (libsource (lib "eagle-import") (part "R-EU_R0603"))
    )
    (comp (ref "R65")
      (value "1K")
      (footprint "eagle-import:R0603")
      (libsource (lib "eagle-import") (part "R-EU_R0603"))
    )
    (comp (ref "R66")
      (value "1K")
      (footprint "eagle-import:R0603")
      (libsource (lib "eagle-import") (part "R-EU_R0603"))
    )
    (comp (ref "R67")
      (value "1K")
      (footprint "eagle-import:R0603")
      (libsource (lib "eagle-import") (part "R-EU_R0603"))
    )
    (comp (ref "R68")
      (value "1K")
      (footprint "eagle-import:R0603")
      (libsource (lib "eagle-import") (part "R-EU_R0603"))
    )
    (comp (ref "R69")
      (value "1K")
      (footprint "eagle-import:R0603")
      (libsource (lib "eagle-import") (part "R-EU_R0603"))
    )
    (comp (ref "R70")
      (value "1K")
      (footprint "eagle-import:R0603")
      (libsource (lib "eagle-import") (part "R-EU_R0603"))
    )
    (comp (ref "R71")
      (value "1K")
      (footprint "eagle-import:R0603")
      (libsource (lib "eagle-import") (part "R-EU_R0603"))
    )
    (comp (ref "R72")
      (value "1K")
      (footprint "eagle-import:R0603")
      (libsource (lib "eagle-import") (part "R-EU_R0603"))
    )
    (comp (ref "R73")
      (value "1K")
      (footprint "eagle-import:R0603")
      (libsource (lib "eagle-import") (part "R-EU_R0603"))
    )
    (comp (ref "R74")
      (value "1K")
      (footprint "eagle-import:R0603")
      (libsource (lib "eagle-import") (part "R-EU_R0603"))
    )
    (comp (ref "R75")
      (value "1K")
      (footprint "eagle-import:R0603")
      (libsource (lib "eagle-import") (part "R-EU_R0603"))
    )
    (comp (ref "R76")
      (value "1K")
      (footprint "eagle-import:R0603")
      (libsource (lib "eagle-import") (part "R-EU_R0603"))
    )
    (comp (ref "R77")
      (value "1K")
      (footprint "eagle-import:R0603")
      (libsource (lib "eagle-import") (part "R-EU_R0603"))
    )
    (comp (ref "R78")
      (value "1K")
      (footprint "eagle-import:R0603")
      (libsource (lib "eagle-import") (part "R-EU_R0603"))
    )
    (comp (ref "R79")
      (value "1K")
      (footprint "eagle-import:R0603")
      (libsource (lib "eagle-import") (part "R-EU_R0603"))
    )
    (comp (ref "R80")
      (value "1K")
      (footprint "eagle-import:R0603")
      (libsource (lib "eagle-import") (part "R-EU_R0603"))
    )
    (comp (ref "R81")
      (value "1K")
      (footprint "eagle-import:R0603")
      (libsource (lib "eagle-import") (part "R-EU_R0603"))
    )
    (comp (ref "R82")
      (value "1K")
      (footprint "eagle-import:R0603")
      (libsource (lib "eagle-import") (part "R-EU_R0603"))
    )
    (comp (ref "R83")
      (value "1K")
      (footprint "eagle-import:R0603")
      (libsource (lib "eagle-import") (part "R-EU_R0603"))
    )
    (comp (ref "R84")
      (value "1K")
      (footprint "eagle-import:R0603")
      (libsource (lib "eagle-import") (part "R-EU_R0603"))
    )
    (comp (ref "R85")
      (value "1K")
      (footprint "eagle-import:R0603")
      (libsource (lib "eagle-import") (part "R-EU_R0603"))
    )
    (comp (ref "R86")
      (value "1K")
      (footprint "eagle-import:R0603")
      (libsource (lib "eagle-import") (part "R-EU_R0603"))
    )
    (comp (ref "R87")
      (value "1K")
      (footprint "eagle-import:R0603")
      (libsource (lib "eagle-import") (part "R-EU_R0603"))
    )
    (comp (ref "R88")
      (value "1K")
      (footprint "eagle-import:R0603")
      (libsource (lib "eagle-import") (part "R-EU_R0603"))
    )
    (comp (ref "R89")
      (value "1K")
      (footprint "eagle-import:R0603")
      (libsource (lib "eagle-import") (part "R-EU_R0603"))
    )
    (comp (ref "R90")
      (value "1K")
      (footprint "eagle-import:R0603")
      (libsource (lib "eagle-import") (part "R-EU_R0603"))
    )
    (comp (ref "R91")
      (value "1K")
      (footprint "eagle-import:R0603")
      (libsource (lib "eagle-import") (part "R-EU_R0603"))
    )
    (comp (ref "R92")
      (value "1K")
      (footprint "eagle-import:R0603")
      (libsource (lib "eagle-import") (part "R-EU_R0603"))
    )
    (comp (ref "R93")
      (value "1K")
      (footprint "eagle-import:R0603")
      (libsource (lib "eagle-import") (part "R-EU_R0603"))
    )
    (comp (ref "R94")
      (value "1K")
      (footprint "eagle-import:R0603")
      (libsource (lib "eagle-import") (part "R-EU_R0603"))
    )
    (comp (ref "R95")
      (value "1K")
      (footprint "eagle-import:R0603")
      (libsource (lib "eagle-import") (part "R-EU_R0603"))
    )
    (comp (ref "R96")
      (value "1K")
      (footprint "eagle-import:R0603")
      (libsource (lib "eagle-import") (part "R-EU_R0603"))
    )
    (comp (ref "R97")
      (value "1K")
      (footprint "eagle-import:R0603")
      (libsource (lib "eagle-import") (part "R-EU_R0603"))
    )
    (comp (ref "R98")
      (value "1K")
      (footprint "eagle-import:R0603")
      (libsource (lib "eagle-import") (part "R-EU_R0603"))
    )
    (comp (ref "R99")
      (value "1K")
      (footprint "eagle-import:R0603")
      (libsource (lib "eagle-import") (part "R-EU_R0603"))
    )
    (comp (ref "R100")
      (value "1K")
      (footprint "eagle-import:R0603")
      (libsource (lib "eagle-import") (part "R-EU_R0603"))
    )
    (comp (ref "R101")
      (value "1K")
      (footprint "eagle-import:R0603")
      (libsource (lib "eagle-import") (part "R-EU_R0603"))
    )
    (comp (ref "R102")
      (value "1K")
      (footprint "eagle-import:R0603")
      (libsource (lib "eagle-import") (part "R-EU_R0603"))
    )
    (comp (ref "R103")
      (value "0")
      (footprint "eagle-import:R0603")
      (libsource (lib "eagle-import") (part "R-EU_R0603"))
    )
    (comp (ref "R104")
      (value "0")
      (footprint "eagle-import:R0603")
      (libsource (lib "eagle-import") (part "R-EU_R0603"))
    )
    (comp (ref "R105")
      (value "0")
      (footprint "eagle-import:R0603")
      (libsource (lib "eagle-import") (part "R-EU_R0603"))
    )
    (comp (ref "RFB1")
      (value "29.4K")
      (footprint "eagle-import:R0603")
      (libsource (lib "eagle-import") (part "R-EU_R0603"))
    )
    (comp (ref "RFB2")
      (value "5.76K")
      (footprint "eagle-import:R0603")
      (libsource (lib "eagle-import") (part "R-EU_R0603"))
    )
    (comp (ref "T1")
      (value "BC846A")
      (footprint "eagle-import:SOT23-3")
      (fields (field (name "MF") "ON Semiconductor"))
      (libsource (lib "eagle-import") (part "BC846A"))
    )
    (comp (ref "T2")
      (value "BC846A")
      (footprint "eagle-import:SOT23-3")
      (fields (field (name "MF") "ON Semiconductor"))
      (libsource (lib "eagle-import") (part "BC846A"))
    )
    (comp (ref "T3")
      (value "BC846A")
      (footprint "eagle-import:SOT23-3")
      (fields (field (name "MF") "ON Semiconductor"))
      (libsource (lib "eagle-import") (part "BC846A"))
    )
    (comp (ref "T4")
      (value "BC846A")
      (footprint "eagle-import:SOT23-3")
      (fields (field (name "MF") "ON Semiconductor"))
      (libsource (lib "eagle-import") (part "BC846A"))
    )
    (comp (ref "T5")
      (value "BC846A")
      (footprint "eagle-import:SOT23-3")
      (fields (field (name "MF") "ON Semiconductor"))
      (libsource (lib "eagle-import") (part "BC846A"))
    )
    (comp (ref "T6")
      (value "BC846A")
      (footprint "eagle-import:SOT23-3")
      (fields (field (name "MF") "ON Semiconductor"))
      (libsource (lib "eagle-import") (part "BC846A"))
    )
    (comp (ref "T7")
      (value "BC846A")
      (footprint "eagle-import:SOT23-3")
      (fields (field (name "MF") "ON Semiconductor"))
      (libsource (lib "eagle-import") (part "BC846A"))
    )
    (comp (ref "T8")
      (value "BC846A")
      (footprint "eagle-import:SOT23-3")
      (fields (field (name "MF") "ON Semiconductor"))
      (libsource (lib "eagle-import") (part "BC846A"))
    )
    (comp (ref "T9")
      (value "BC846A")
      (footprint "eagle-import:SOT23-3")
      (fields (field (name "MF") "ON Semiconductor"))
      (libsource (lib "eagle-import") (part "BC846A"))
    )
    (comp (ref "T10")
      (value "BC846A")
      (footprint "eagle-import:SOT23-3")
      (fields (field (name "MF") "ON Semiconductor") (field (name "SPICEPREFIX") "J"))
      (libsource (lib "eagle-import") (part "BC846A"))
    )
    (comp (ref "T11")
      (value "BC846A")
      (footprint "eagle-import:SOT23-3")
      (fields (field (name "MF") "ON Semiconductor"))
      (libsource (lib "eagle-import") (part "BC846A"))
    )
    (comp (ref "T12")
      (value "BC846A")
      (footprint "eagle-import:SOT23-3")
      (fields (field (name "MF") "ON Semiconductor"))
      (libsource (lib "eagle-import") (part "BC846A"))
    )
    (comp (ref "T13")
      (value "BC846A")
      (footprint "eagle-import:SOT23-3")
      (fields (field (name "MF") "ON Semiconductor"))
      (libsource (lib "eagle-import") (part "BC846A"))
    )
    (comp (ref "T14")
      (value "BC846A")
      (footprint "eagle-import:SOT23-3")
      (fields (field (name "MF") "ON Semiconductor"))
      (libsource (lib "eagle-import") (part "BC846A"))
    )
    (comp (ref "T15")
      (value "BC846A")
      (footprint "eagle-import:SOT23-3")
      (fields (field (name "MF") "ON Semiconductor"))
      (libsource (lib "eagle-import") (part "BC846A"))
    )
    (comp (ref "T16")
      (value "BC846A")
      (footprint "eagle-import:SOT23-3")
      (fields (field (name "MF") "ON Semiconductor"))
      (libsource (lib "eagle-import") (part "BC846A"))
    )
    (comp (ref "T17")
      (value "BC846A")
      (footprint "eagle-import:SOT23-3")
      (fields (field (name "MF") "ON Semiconductor"))
      (libsource (lib "eagle-import") (part "BC846A"))
    )
    (comp (ref "T18")
      (value "BC846A")
      (footprint "eagle-import:SOT23-3")
      (fields (field (name "MF") "ON Semiconductor"))
      (libsource (lib "eagle-import") (part "BC846A"))
    )
    (comp (ref "T19")
      (value "BC846A")
      (footprint "eagle-import:SOT23-3")
      (fields (field (name "MF") "ON Semiconductor"))
      (libsource (lib "eagle-import") (part "BC846A"))
    )
    (comp (ref "T20")
      (value "BC846A")
      (footprint "eagle-import:SOT23-3")
      (fields (field (name "MF") "ON Semiconductor"))
      (libsource (lib "eagle-import") (part "BC846A"))
    )
    (comp (ref "T21")
      (value "BC846A")
      (footprint "eagle-import:SOT23-3")
      (fields (field (name "MF") "ON Semiconductor"))
      (libsource (lib "eagle-import") (part "BC846A"))
    )
    (comp (ref "T22")
      (value "BC846A")
      (footprint "eagle-import:SOT23-3")
      (fields (field (name "MF") "ON Semiconductor"))
      (libsource (lib "eagle-import") (part "BC846A"))
    )
    (comp (ref "T23")
      (value "BC846A")
      (footprint "eagle-import:SOT23-3")
      (fields (field (name "MF") "ON Semiconductor"))
      (libsource (lib "eagle-import") (part "BC846A"))
    )
    (comp (ref "T24")
      (value "BC846A")
      (footprint "eagle-import:SOT23-3")
      (fields (field (name "MF") "ON Semiconductor"))
      (libsource (lib "eagle-import") (part "BC846A"))
    )
    (comp (ref "T25")
      (value "BC846A")
      (footprint "eagle-import:SOT23-3")
      (fields (field (name "MF") "ON Semiconductor"))
      (libsource (lib "eagle-import") (part "BC846A"))
    )
    (comp (ref "T26")
      (value "BC846A")
      (footprint "eagle-import:SOT23-3")
      (fields (field (name "MF") "ON Semiconductor"))
      (libsource (lib "eagle-import") (part "BC846A"))
    )
    (comp (ref "T27")
      (value "BC846A")
      (footprint "eagle-import:SOT23-3")
      (fields (field (name "MF") "ON Semiconductor"))
      (libsource (lib "eagle-import") (part "BC846A"))
    )
    (comp (ref "T28")
      (value "BC846A")
      (footprint "eagle-import:SOT23-3")
      (fields (field (name "MF") "ON Semiconductor"))
      (libsource (lib "eagle-import") (part "BC846A"))
    )
    (comp (ref "T29")
      (value "BC846A")
      (footprint "eagle-import:SOT23-3")
      (fields (field (name "MF") "ON Semiconductor"))
      (libsource (lib "eagle-import") (part "BC846A"))
    )
    (comp (ref "T30")
      (value "BC846A")
      (footprint "eagle-import:SOT23-3")
      (fields (field (name "MF") "ON Semiconductor"))
      (libsource (lib "eagle-import") (part "BC846A"))
    )
    (comp (ref "U1")
      (value "LM2611")
      (footprint "eagle-import:SOT95P280X145-5N")
      (fields (field (name "MF") "Texas Instruments") (field (name "MP") "LM2611BMFX/NOPB"))
      (libsource (lib "eagle-import") (part "LM2611BMFX/NOPB"))
    )
    (comp (ref "U2")
      (value "LMR62014")
      (footprint "eagle-import:SOT95P280X145-5N")
      (fields (field (name "MF") "Texas Instruments") (field (name "MP") "LMR62014XMF/NOPB"))
      (libsource (lib "eagle-import") (part "LMR62014XMF/NOPB"))
    )
  )
  (nets
    (net (code "1") (name "+7,5V") (class "Default")
      (node (ref "C45") (pin "2") (pinfunction "2_2") (pintype "passive"))
      (node (ref "C46") (pin "1") (pinfunction "1_1") (pintype "passive"))
      (node (ref "C47") (pin "1") (pinfunction "1_1") (pintype "passive"))
      (node (ref "C7") (pin "1") (pinfunction "1_1") (pintype "passive"))
      (node (ref "CF") (pin "1") (pinfunction "1_1") (pintype "passive"))
      (node (ref "CIN") (pin "1") (pinfunction "1_1") (pintype "passive"))
      (node (ref "D7") (pin "1") (pinfunction "C_1") (pintype "passive"))
      (node (ref "L2") (pin "1") (pinfunction "1_1") (pintype "passive"))
      (node (ref "R27") (pin "1") (pinfunction "1_1") (pintype "passive"))
      (node (ref "R31") (pin "2") (pinfunction "2_2") (pintype "passive"))
      (node (ref "U1") (pin "4") (pinfunction "~{SHDN}_4") (pintype "input"))
      (node (ref "U1") (pin "5") (pinfunction "VIN_5") (pintype "input"))
    )
    (net (code "2") (name "/-7,5V") (class "Default")
      (node (ref "C48") (pin "2") (pinfunction "2_2") (pintype "passive"))
      (node (ref "C49") (pin "1") (pinfunction "1_1") (pintype "passive"))
      (node (ref "C50") (pin "1") (pinfunction "1_1") (pintype "passive"))
      (node (ref "CFF") (pin "1") (pinfunction "1_1") (pintype "passive"))
      (node (ref "COUT") (pin "1") (pinfunction "1_1") (pintype "passive"))
      (node (ref "L3") (pin "2") (pinfunction "2_2") (pintype "passive"))
      (node (ref "R105") (pin "1") (pinfunction "1_1") (pintype "passive"))
      (node (ref "RFB1") (pin "1") (pinfunction "1_1") (pintype "passive"))
    )
    (net (code "3") (name "BP1_OUT") (class "Default")
      (node (ref "D101") (pin "2") (pinfunction "A_2") (pintype "passive"))
      (node (ref "IC2") (pin "13") (pinfunction "-IN_13") (pintype "input"))
      (node (ref "IC2") (pin "14") (pinfunction "OUT_14") (pintype "output"))
    )
    (net (code "4") (name "BP2_OUT") (class "Default")
      (node (ref "D102") (pin "2") (pinfunction "A_2") (pintype "passive"))
      (node (ref "IC3") (pin "13") (pinfunction "-IN_13") (pintype "input"))
      (node (ref "IC3") (pin "14") (pinfunction "OUT_14") (pintype "output"))
    )
    (net (code "5") (name "BP3_OUT") (class "Default")
      (node (ref "D103") (pin "2") (pinfunction "A_2") (pintype "passive"))
      (node (ref "IC4") (pin "13") (pinfunction "-IN_13") (pintype "input"))
      (node (ref "IC4") (pin "14") (pinfunction "OUT_14") (pintype "output"))
    )
    (net (code "6") (name "GND") (class "Default")
      (node (ref "C1") (pin "2") (pinfunction "2_2") (pintype "passive"))
      (node (ref "C10") (pin "1") (pinfunction "1_1") (pintype "passive"))
      (node (ref "C11") (pin "1") (pinfunction "1_1") (pintype "passive"))
      (node (ref "C12") (pin "1") (pinfunction "1_1") (pintype "passive"))
      (node (ref "C13") (pin "1") (pinfunction "1_1") (pintype "passive"))
      (node (ref "C14") (pin "1") (pinfunction "1_1") (pintype "passive"))
      (node (ref "C2") (pin "2") (pinfunction "2_2") (pintype "passive"))
      (node (ref "C27") (pin "2") (pinfunction "2_2") (pintype "passive"))
      (node (ref "C28") (pin "2") (pinfunction "2_2") (pintype "passive"))
      (node (ref "C29") (pin "2") (pinfunction "2_2") (pintype "passive"))
      (node (ref "C3") (pin "2") (pinfunction "2_2") (pintype "passive"))
      (node (ref "C32") (pin "2") (pinfunction "2_2") (pintype "passive"))
      (node (ref "C33") (pin "2") (pinfunction "2_2") (pintype "passive"))
      (node (ref "C34") (pin "2") (pinfunction "2_2") (pintype "passive"))
      (node (ref "C35") (pin "2") (pinfunction "2_2") (pintype "passive"))
      (node (ref "C36") (pin "2") (pinfunction "2_2") (pintype "passive"))
      (node (ref "C37") (pin "2") (pinfunction "2_2") (pintype "passive"))
      (node (ref "C39") (pin "2") (pinfunction "2_2") (pintype "passive"))
      (node (ref "C4") (pin "1") (pinfunction "1_1") (pintype "passive"))
      (node (ref "C40") (pin "1") (pinfunction "1_1") (pintype "passive"))
      (node (ref "C41") (pin "2") (pinfunction "2_2") (pintype "passive"))
      (node (ref "C42") (pin "2") (pinfunction "2_2") (pintype "passive"))
      (node (ref "C43") (pin "2") (pinfunction "2_2") (pintype "passive"))
      (node (ref "C44") (pin "2") (pinfunction "2_2") (pintype "passive"))
      (node (ref "C45") (pin "1") (pinfunction "1_1") (pintype "passive"))
      (node (ref "C46") (pin "2") (pinfunction "2_2") (pintype "passive"))
      (node (ref "C47") (pin "2") (pinfunction "2_2") (pintype "passive"))
      (node (ref "C48") (pin "1") (pinfunction "1_1") (pintype "passive"))
      (node (ref "C49") (pin "2") (pinfunction "2_2") (pintype "passive"))
      (node (ref "C5") (pin "2") (pinfunction "2_2") (pintype "passive"))
      (node (ref "C50") (pin "2") (pinfunction "2_2") (pintype "passive"))
      (node (ref "C6") (pin "2") (pinfunction "2_2") (pintype "passive"))
      (node (ref "C7") (pin "2") (pinfunction "2_2") (pintype "passive"))
      (node (ref "C8") (pin "1") (pinfunction "1_1") (pintype "passive"))
      (node (ref "C9") (pin "2") (pinfunction "2_2") (pintype "passive"))
      (node (ref "CIN") (pin "2") (pinfunction "2_2") (pintype "passive"))
      (node (ref "COUT") (pin "2") (pinfunction "2_2") (pintype "passive"))
      (node (ref "D14") (pin "1") (pinfunction "C_1") (pintype "passive"))
      (node (ref "IC1") (pin "3") (pinfunction "+IN_3") (pintype "input"))
      (node (ref "IC1") (pin "5") (pinfunction "+IN_5") (pintype "input"))
      (node (ref "IC2") (pin "10") (pinfunction "+IN_10") (pintype "input"))
      (node (ref "IC2") (pin "3") (pinfunction "+IN_3") (pintype "input"))
      (node (ref "IC2") (pin "5") (pinfunction "+IN_5") (pintype "input"))
      (node (ref "IC3") (pin "10") (pinfunction "+IN_10") (pintype "input"))
      (node (ref "IC3") (pin "3") (pinfunction "+IN_3") (pintype "input"))
      (node (ref "IC3") (pin "5") (pinfunction "+IN_5") (pintype "input"))
      (node (ref "IC4") (pin "10") (pinfunction "+IN_10") (pintype "input"))
      (node (ref "IC4") (pin "3") (pinfunction "+IN_3") (pintype "input"))
      (node (ref "IC4") (pin "5") (pinfunction "+IN_5") (pintype "input"))
      (node (ref "IC5") (pin "5") (pinfunction "+IN_5") (pintype "input"))
      (node (ref "IC7") (pin "5") (pinfunction "+IN_5") (pintype "input"))
      (node (ref "J2") (pin "3") (pinfunction "3_3") (pintype "passive"))
      (node (ref "R14") (pin "1") (pinfunction "1_1") (pintype "passive"))
      (node (ref "R17") (pin "1") (pinfunction "1_1") (pintype "passive"))
      (node (ref "R2") (pin "1") (pinfunction "1_1") (pintype "passive"))
      (node (ref "R20") (pin "1") (pinfunction "1_1") (pintype "passive"))
      (node (ref "R34") (pin "1") (pinfunction "1_1") (pintype "passive"))
      (node (ref "R35") (pin "2") (pinfunction "2_2") (pintype "passive"))
      (node (ref "R37") (pin "1") (pinfunction "1_1") (pintype "passive"))
      (node (ref "R39") (pin "2") (pinfunction "2_2") (pintype "passive"))
      (node (ref "R5") (pin "1") (pinfunction "1_1") (pintype "passive"))
      (node (ref "RFB2") (pin "2") (pinfunction "2_2") (pintype "passive"))
      (node (ref "T1") (pin "2") (pinfunction "E_2") (pintype "bidirectional"))
      (node (ref "T10") (pin "2") (pinfunction "E_2") (pintype "bidirectional"))
      (node (ref "T11") (pin "2") (pinfunction "E_2") (pintype "bidirectional"))
      (node (ref "T12") (pin "2") (pinfunction "E_2") (pintype "bidirectional"))
      (node (ref "T13") (pin "2") (pinfunction "E_2") (pintype "bidirectional"))
      (node (ref "T14") (pin "2") (pinfunction "E_2") (pintype "bidirectional"))
      (node (ref "T15") (pin "2") (pinfunction "E_2") (pintype "bidirectional"))
      (node (ref "T16") (pin "2") (pinfunction "E_2") (pintype "bidirectional"))
      (node (ref "T17") (pin "2") (pinfunction "E_2") (pintype "bidirectional"))
      (node (ref "T18") (pin "2") (pinfunction "E_2") (pintype "bidirectional"))
      (node (ref "T19") (pin "2") (pinfunction "E_2") (pintype "bidirectional"))
      (node (ref "T2") (pin "2") (pinfunction "E_2") (pintype "bidirectional"))
      (node (ref "T20") (pin "2") (pinfunction "E_2") (pintype "bidirectional"))
      (node (ref "T21") (pin "2") (pinfunction "E_2") (pintype "bidirectional"))
      (node (ref "T22") (pin "2") (pinfunction "E_2") (pintype "bidirectional"))
      (node (ref "T23") (pin "2") (pinfunction "E_2") (pintype "bidirectional"))
      (node (ref "T24") (pin "2") (pinfunction "E_2") (pintype "bidirectional"))
      (node (ref "T25") (pin "2") (pinfunction "E_2") (pintype "bidirectional"))
      (node (ref "T26") (pin "2") (pinfunction "E_2") (pintype "bidirectional"))
      (node (ref "T27") (pin "2") (pinfunction "E_2") (pintype "bidirectional"))
      (node (ref "T28") (pin "2") (pinfunction "E_2") (pintype "bidirectional"))
      (node (ref "T29") (pin "2") (pinfunction "E_2") (pintype "bidirectional"))
      (node (ref "T3") (pin "2") (pinfunction "E_2") (pintype "bidirectional"))
      (node (ref "T30") (pin "2") (pinfunction "E_2") (pintype "bidirectional"))
      (node (ref "T4") (pin "2") (pinfunction "E_2") (pintype "bidirectional"))
      (node (ref "T5") (pin "2") (pinfunction "E_2") (pintype "bidirectional"))
      (node (ref "T6") (pin "2") (pinfunction "E_2") (pintype "bidirectional"))
      (node (ref "T7") (pin "2") (pinfunction "E_2") (pintype "bidirectional"))
      (node (ref "T8") (pin "2") (pinfunction "E_2") (pintype "bidirectional"))
      (node (ref "T9") (pin "2") (pinfunction "E_2") (pintype "bidirectional"))
      (node (ref "U1") (pin "2") (pinfunction "GND_2") (pintype "power_in"))
      (node (ref "U2") (pin "2") (pinfunction "GND_2") (pintype "power_in"))
    )
    (net (code "7") (name "HP_OUT") (class "Default")
      (node (ref "D104") (pin "2") (pinfunction "A_2") (pintype "passive"))
      (node (ref "IC7") (pin "7") (pinfunction "OUT_7") (pintype "output"))
      (node (ref "R24") (pin "2") (pinfunction "2_2") (pintype "passive"))
    )
    (net (code "8") (name "IN2,1V") (class "Default")
      (node (ref "C38") (pin "2") (pinfunction "2_2") (pintype "passive"))
      (node (ref "J2") (pin "1") (pinfunction "1_1") (pintype "passive"))
    )
    (net (code "9") (name "MAIN-5V") (class "Default")
      (node (ref "C14") (pin "2") (pinfunction "2_2") (pintype "passive"))
      (node (ref "C43") (pin "1") (pinfunction "1_1") (pintype "passive"))
      (node (ref "C44") (pin "1") (pinfunction "1_1") (pintype "passive"))
      (node (ref "J2") (pin "4") (pinfunction "4_4") (pintype "passive"))
      (node (ref "R103") (pin "1") (pinfunction "1_1") (pintype "passive"))
    )
    (net (code "10") (name "Net-(C1-Pad1)") (class "Default")
      (node (ref "C1") (pin "1") (pinfunction "1_1") (pintype "passive"))
      (node (ref "C6") (pin "1") (pinfunction "1_1") (pintype "passive"))
      (node (ref "R8") (pin "2") (pinfunction "2_2") (pintype "passive"))
      (node (ref "R9") (pin "1") (pinfunction "1_1") (pintype "passive"))
    )
    (net (code "11") (name "Net-(C2-Pad1)") (class "Default")
      (node (ref "C2") (pin "1") (pinfunction "1_1") (pintype "passive"))
      (node (ref "C3") (pin "1") (pinfunction "1_1") (pintype "passive"))
      (node (ref "R7") (pin "2") (pinfunction "2_2") (pintype "passive"))
      (node (ref "R8") (pin "1") (pinfunction "1_1") (pintype "passive"))
    )
    (net (code "12") (name "Net-(C15-Pad2)") (class "Default")
      (node (ref "C15") (pin "2") (pinfunction "2_2") (pintype "passive"))
      (node (ref "C16") (pin "1") (pinfunction "1_1") (pintype "passive"))
      (node (ref "R1") (pin "2") (pinfunction "2_2") (pintype "passive"))
      (node (ref "R2") (pin "2") (pinfunction "2_2") (pintype "passive"))
    )
    (net (code "13") (name "Net-(C17-Pad1)") (class "Default")
      (node (ref "C17") (pin "1") (pinfunction "1_1") (pintype "passive"))
      (node (ref "R29") (pin "2") (pinfunction "2_2") (pintype "passive"))
    )
    (net (code "14") (name "Net-(C17-Pad2)") (class "Default")
      (node (ref "C17") (pin "2") (pinfunction "2_2") (pintype "passive"))
      (node (ref "C18") (pin "1") (pinfunction "1_1") (pintype "passive"))
      (node (ref "R4") (pin "2") (pinfunction "2_2") (pintype "passive"))
      (node (ref "R5") (pin "2") (pinfunction "2_2") (pintype "passive"))
    )
    (net (code "15") (name "Net-(C19-Pad2)") (class "Default")
      (node (ref "C19") (pin "2") (pinfunction "2_2") (pintype "passive"))
      (node (ref "C20") (pin "1") (pinfunction "1_1") (pintype "passive"))
      (node (ref "R13") (pin "2") (pinfunction "2_2") (pintype "passive"))
      (node (ref "R14") (pin "2") (pinfunction "2_2") (pintype "passive"))
    )
    (net (code "16") (name "Net-(C21-Pad2)") (class "Default")
      (node (ref "C21") (pin "2") (pinfunction "2_2") (pintype "passive"))
      (node (ref "C22") (pin "1") (pinfunction "1_1") (pintype "passive"))
      (node (ref "R16") (pin "2") (pinfunction "2_2") (pintype "passive"))
      (node (ref "R17") (pin "2") (pinfunction "2_2") (pintype "passive"))
    )
    (net (code "17") (name "Net-(C23-Pad2)") (class "Default")
      (node (ref "C23") (pin "2") (pinfunction "2_2") (pintype "passive"))
      (node (ref "C24") (pin "1") (pinfunction "1_1") (pintype "passive"))
      (node (ref "R33") (pin "2") (pinfunction "2_2") (pintype "passive"))
      (node (ref "R34") (pin "2") (pinfunction "2_2") (pintype "passive"))
    )
    (net (code "18") (name "Net-(C25-Pad2)") (class "Default")
      (node (ref "C25") (pin "2") (pinfunction "2_2") (pintype "passive"))
      (node (ref "C26") (pin "1") (pinfunction "1_1") (pintype "passive"))
      (node (ref "R36") (pin "2") (pinfunction "2_2") (pintype "passive"))
      (node (ref "R37") (pin "2") (pinfunction "2_2") (pintype "passive"))
    )
    (net (code "19") (name "Net-(C30-Pad1)") (class "Default")
      (node (ref "C30") (pin "1") (pinfunction "1_1") (pintype "passive"))
      (node (ref "C31") (pin "2") (pinfunction "2_2") (pintype "passive"))
      (node (ref "R21") (pin "2") (pinfunction "2_2") (pintype "passive"))
    )
    (net (code "20") (name "Net-(D1-PadC)") (class "Default")
      (node (ref "D1") (pin "C") (pinfunction "C_C") (pintype "passive"))
      (node (ref "D2") (pin "A") (pinfunction "A_A") (pintype "passive"))
      (node (ref "R54") (pin "2") (pinfunction "2_2") (pintype "passive"))
    )
    (net (code "21") (name "Net-(D2-PadC)") (class "Default")
      (node (ref "D2") (pin "C") (pinfunction "C_C") (pintype "passive"))
      (node (ref "D3") (pin "A") (pinfunction "A_A") (pintype "passive"))
      (node (ref "R53") (pin "2") (pinfunction "2_2") (pintype "passive"))
    )
    (net (code "22") (name "Net-(D3-PadC)") (class "Default")
      (node (ref "D3") (pin "C") (pinfunction "C_C") (pintype "passive"))
      (node (ref "D4") (pin "A") (pinfunction "A_A") (pintype "passive"))
      (node (ref "R52") (pin "2") (pinfunction "2_2") (pintype "passive"))
    )
    (net (code "23") (name "Net-(D4-PadC)") (class "Default")
      (node (ref "D4") (pin "C") (pinfunction "C_C") (pintype "passive"))
      (node (ref "D6") (pin "A") (pinfunction "A_A") (pintype "passive"))
      (node (ref "R51") (pin "2") (pinfunction "2_2") (pintype "passive"))
    )
    (net (code "24") (name "Net-(D5-PadA)") (class "Default")
      (node (ref "D5") (pin "A") (pinfunction "A_A") (pintype "passive"))
      (node (ref "D6") (pin "C") (pinfunction "C_C") (pintype "passive"))
      (node (ref "R50") (pin "2") (pinfunction "2_2") (pintype "passive"))
    )
    (net (code "25") (name "Net-(D5-PadC)") (class "Default")
      (node (ref "D5") (pin "C") (pinfunction "C_C") (pintype "passive"))
      (node (ref "R49") (pin "2") (pinfunction "2_2") (pintype "passive"))
    )
    (net (code "26") (name "Net-(D7-A)") (class "Default")
      (node (ref "D7") (pin "2") (pinfunction "A_2") (pintype "passive"))
      (node (ref "L1") (pin "2") (pinfunction "2_2") (pintype "passive"))
      (node (ref "U2") (pin "1") (pinfunction "SW_1") (pintype "output"))
    )
    (net (code "27") (name "Net-(D8-PadC)") (class "Default")
      (node (ref "D8") (pin "C") (pinfunction "C_C") (pintype "passive"))
      (node (ref "D9") (pin "A") (pinfunction "A_A") (pintype "passive"))
      (node (ref "R65") (pin "2") (pinfunction "2_2") (pintype "passive"))
    )
    (net (code "28") (name "Net-(D10-PadA)") (class "Default")
      (node (ref "D10") (pin "A") (pinfunction "A_A") (pintype "passive"))
      (node (ref "D9") (pin "C") (pinfunction "C_C") (pintype "passive"))
      (node (ref "R64") (pin "2") (pinfunction "2_2") (pintype "passive"))
    )
    (net (code "29") (name "Net-(D10-PadC)") (class "Default")
      (node (ref "D10") (pin "C") (pinfunction "C_C") (pintype "passive"))
      (node (ref "D11") (pin "A") (pinfunction "A_A") (pintype "passive"))
      (node (ref "R63") (pin "2") (pinfunction "2_2") (pintype "passive"))
    )
    (net (code "30") (name "Net-(D11-PadC)") (class "Default")
      (node (ref "D11") (pin "C") (pinfunction "C_C") (pintype "passive"))
      (node (ref "D12") (pin "A") (pinfunction "A_A") (pintype "passive"))
      (node (ref "R62") (pin "2") (pinfunction "2_2") (pintype "passive"))
    )
    (net (code "31") (name "Net-(D12-PadC)") (class "Default")
      (node (ref "D12") (pin "C") (pinfunction "C_C") (pintype "passive"))
      (node (ref "R61") (pin "2") (pinfunction "2_2") (pintype "passive"))
    )
    (net (code "32") (name "Net-(D13-PadC)") (class "Default")
      (node (ref "D13") (pin "C") (pinfunction "C_C") (pintype "passive"))
      (node (ref "D15") (pin "A") (pinfunction "A_A") (pintype "passive"))
      (node (ref "R78") (pin "2") (pinfunction "2_2") (pintype "passive"))
    )
    (net (code "33") (name "Net-(D14-A)") (class "Default")
      (node (ref "CCUK") (pin "2") (pinfunction "2_2") (pintype "passive"))
      (node (ref "D14") (pin "2") (pinfunction "A_2") (pintype "passive"))
      (node (ref "L3") (pin "1") (pinfunction "1_1") (pintype "passive"))
    )
    (net (code "34") (name "Net-(D15-PadC)") (class "Default")
      (node (ref "D15") (pin "C") (pinfunction "C_C") (pintype "passive"))
      (node (ref "D17") (pin "A") (pinfunction "A_A") (pintype "passive"))
      (node (ref "R77") (pin "2") (pinfunction "2_2") (pintype "passive"))
    )
    (net (code "35") (name "Net-(D16-PadC)") (class "Default")
      (node (ref "D16") (pin "C") (pinfunction "C_C") (pintype "passive"))
      (node (ref "D8") (pin "A") (pinfunction "A_A") (pintype "passive"))
      (node (ref "R66") (pin "2") (pinfunction "2_2") (pintype "passive"))
    )
    (net (code "36") (name "Net-(D17-PadC)") (class "Default")
      (node (ref "D17") (pin "C") (pinfunction "C_C") (pintype "passive"))
      (node (ref "D18") (pin "A") (pinfunction "A_A") (pintype "passive"))
      (node (ref "R76") (pin "2") (pinfunction "2_2") (pintype "passive"))
    )
    (net (code "37") (name "Net-(D18-PadC)") (class "Default")
      (node (ref "D18") (pin "C") (pinfunction "C_C") (pintype "passive"))
      (node (ref "D19") (pin "A") (pinfunction "A_A") (pintype "passive"))
      (node (ref "R75") (pin "2") (pinfunction "2_2") (pintype "passive"))
    )
    (net (code "38") (name "Net-(D19-PadC)") (class "Default")
      (node (ref "D19") (pin "C") (pinfunction "C_C") (pintype "passive"))
      (node (ref "D20") (pin "A") (pinfunction "A_A") (pintype "passive"))
      (node (ref "R74") (pin "2") (pinfunction "2_2") (pintype "passive"))
    )
    (net (code "39") (name "Net-(D20-PadC)") (class "Default")
      (node (ref "D20") (pin "C") (pinfunction "C_C") (pintype "passive"))
      (node (ref "R73") (pin "2") (pinfunction "2_2") (pintype "passive"))
    )
    (net (code "40") (name "Net-(D22-PadC)") (class "Default")
      (node (ref "D22") (pin "C") (pinfunction "C_C") (pintype "passive"))
      (node (ref "D23") (pin "A") (pinfunction "A_A") (pintype "passive"))
      (node (ref "R90") (pin "2") (pinfunction "2_2") (pintype "passive"))
    )
    (net (code "41") (name "Net-(D23-PadC)") (class "Default")
      (node (ref "D23") (pin "C") (pinfunction "C_C") (pintype "passive"))
      (node (ref "D24") (pin "A") (pinfunction "A_A") (pintype "passive"))
      (node (ref "R89") (pin "2") (pinfunction "2_2") (pintype "passive"))
    )
    (net (code "42") (name "Net-(D24-PadC)") (class "Default")
      (node (ref "D24") (pin "C") (pinfunction "C_C") (pintype "passive"))
      (node (ref "D25") (pin "A") (pinfunction "A_A") (pintype "passive"))
      (node (ref "R88") (pin "2") (pinfunction "2_2") (pintype "passive"))
    )
    (net (code "43") (name "Net-(D25-PadC)") (class "Default")
      (node (ref "D25") (pin "C") (pinfunction "C_C") (pintype "passive"))
      (node (ref "D26") (pin "A") (pinfunction "A_A") (pintype "passive"))
      (node (ref "R87") (pin "2") (pinfunction "2_2") (pintype "passive"))
    )
    (net (code "44") (name "Net-(D26-PadC)") (class "Default")
      (node (ref "D26") (pin "C") (pinfunction "C_C") (pintype "passive"))
      (node (ref "D27") (pin "A") (pinfunction "A_A") (pintype "passive"))
      (node (ref "R86") (pin "2") (pinfunction "2_2") (pintype "passive"))
    )
    (net (code "45") (name "Net-(D27-PadC)") (class "Default")
      (node (ref "D27") (pin "C") (pinfunction "C_C") (pintype "passive"))
      (node (ref "R85") (pin "2") (pinfunction "2_2") (pintype "passive"))
    )
    (net (code "46") (name "Net-(D29-PadC)") (class "Default")
      (node (ref "D29") (pin "C") (pinfunction "C_C") (pintype "passive"))
      (node (ref "D30") (pin "A") (pinfunction "A_A") (pintype "passive"))
      (node (ref "R102") (pin "2") (pinfunction "2_2") (pintype "passive"))
    )
    (net (code "47") (name "Net-(D30-PadC)") (class "Default")
      (node (ref "D30") (pin "C") (pinfunction "C_C") (pintype "passive"))
      (node (ref "D31") (pin "A") (pinfunction "A_A") (pintype "passive"))
      (node (ref "R101") (pin "2") (pinfunction "2_2") (pintype "passive"))
    )
    (net (code "48") (name "Net-(D31-PadC)") (class "Default")
      (node (ref "D31") (pin "C") (pinfunction "C_C") (pintype "passive"))
      (node (ref "D32") (pin "A") (pinfunction "A_A") (pintype "passive"))
      (node (ref "R100") (pin "2") (pinfunction "2_2") (pintype "passive"))
    )
    (net (code "49") (name "Net-(D32-PadC)") (class "Default")
      (node (ref "D32") (pin "C") (pinfunction "C_C") (pintype "passive"))
      (node (ref "D33") (pin "A") (pinfunction "A_A") (pintype "passive"))
      (node (ref "R99") (pin "2") (pinfunction "2_2") (pintype "passive"))
    )
    (net (code "50") (name "Net-(D33-PadC)") (class "Default")
      (node (ref "D33") (pin "C") (pinfunction "C_C") (pintype "passive"))
      (node (ref "D34") (pin "A") (pinfunction "A_A") (pintype "passive"))
      (node (ref "R98") (pin "2") (pinfunction "2_2") (pintype "passive"))
    )
    (net (code "51") (name "Net-(D34-PadC)") (class "Default")
      (node (ref "D34") (pin "C") (pinfunction "C_C") (pintype "passive"))
      (node (ref "R97") (pin "2") (pinfunction "2_2") (pintype "passive"))
    )
    (net (code "52") (name "Net-(D100-C)") (class "Default")
      (node (ref "C33") (pin "1") (pinfunction "1_1") (pintype "passive"))
      (node (ref "D1") (pin "A") (pinfunction "A_A") (pintype "passive"))
      (node (ref "D100") (pin "1") (pinfunction "C_1") (pintype "passive"))
    )
    (net (code "53") (name "Net-(D101-C)") (class "Default")
      (node (ref "C34") (pin "1") (pinfunction "1_1") (pintype "passive"))
      (node (ref "D101") (pin "1") (pinfunction "C_1") (pintype "passive"))
      (node (ref "D16") (pin "A") (pinfunction "A_A") (pintype "passive"))
    )
    (net (code "54") (name "Net-(D102-C)") (class "Default")
      (node (ref "C35") (pin "1") (pinfunction "1_1") (pintype "passive"))
      (node (ref "D102") (pin "1") (pinfunction "C_1") (pintype "passive"))
      (node (ref "D13") (pin "A") (pinfunction "A_A") (pintype "passive"))
    )
    (net (code "55") (name "Net-(D103-C)") (class "Default")
      (node (ref "C36") (pin "1") (pinfunction "1_1") (pintype "passive"))
      (node (ref "D103") (pin "1") (pinfunction "C_1") (pintype "passive"))
      (node (ref "D22") (pin "A") (pinfunction "A_A") (pintype "passive"))
    )
    (net (code "56") (name "Net-(D104-C)") (class "Default")
      (node (ref "C37") (pin "1") (pinfunction "1_1") (pintype "passive"))
      (node (ref "D104") (pin "1") (pinfunction "C_1") (pintype "passive"))
      (node (ref "D29") (pin "A") (pinfunction "A_A") (pintype "passive"))
    )
    (net (code "57") (name "Net-(IC1A--IN)") (class "Default")
      (node (ref "IC1") (pin "2") (pinfunction "-IN_2") (pintype "input"))
      (node (ref "R10") (pin "1") (pinfunction "1_1") (pintype "passive"))
      (node (ref "R9") (pin "2") (pinfunction "2_2") (pintype "passive"))
    )
    (net (code "58") (name "Net-(IC1A-OUT)") (class "Default")
      (node (ref "IC1") (pin "1") (pinfunction "OUT_1") (pintype "output"))
      (node (ref "R10") (pin "2") (pinfunction "2_2") (pintype "passive"))
      (node (ref "R11") (pin "1") (pinfunction "1_1") (pintype "passive"))
    )
    (net (code "59") (name "Net-(IC1B--IN)") (class "Default")
      (node (ref "IC1") (pin "6") (pinfunction "-IN_6") (pintype "input"))
      (node (ref "R11") (pin "2") (pinfunction "2_2") (pintype "passive"))
      (node (ref "R12") (pin "1") (pinfunction "1_1") (pintype "passive"))
    )
    (net (code "60") (name "Net-(IC2A--IN)") (class "Default")
      (node (ref "C16") (pin "2") (pinfunction "2_2") (pintype "passive"))
      (node (ref "IC2") (pin "2") (pinfunction "-IN_2") (pintype "input"))
      (node (ref "R28") (pin "1") (pinfunction "1_1") (pintype "passive"))
    )
    (net (code "61") (name "Net-(IC2A-OUT)") (class "Default")
      (node (ref "C15") (pin "1") (pinfunction "1_1") (pintype "passive"))
      (node (ref "IC2") (pin "1") (pinfunction "OUT_1") (pintype "output"))
      (node (ref "R28") (pin "2") (pinfunction "2_2") (pintype "passive"))
      (node (ref "R4") (pin "1") (pinfunction "1_1") (pintype "passive"))
    )
    (net (code "62") (name "Net-(IC2B--IN)") (class "Default")
      (node (ref "C18") (pin "2") (pinfunction "2_2") (pintype "passive"))
      (node (ref "IC2") (pin "6") (pinfunction "-IN_6") (pintype "input"))
      (node (ref "R29") (pin "1") (pinfunction "1_1") (pintype "passive"))
    )
    (net (code "63") (name "Net-(IC2B-OUT)") (class "Default")
      (node (ref "IC2") (pin "7") (pinfunction "OUT_7") (pintype "output"))
      (node (ref "R3") (pin "1") (pinfunction "1_1") (pintype "passive"))
    )
    (net (code "64") (name "Net-(IC2C--IN)") (class "Default")
      (node (ref "IC2") (pin "9") (pinfunction "-IN_9") (pintype "input"))
      (node (ref "R3") (pin "2") (pinfunction "2_2") (pintype "passive"))
      (node (ref "R6") (pin "1") (pinfunction "1_1") (pintype "passive"))
    )
    (net (code "65") (name "Net-(IC2C-OUT)") (class "Default")
      (node (ref "IC2") (pin "12") (pinfunction "+IN_12") (pintype "input"))
      (node (ref "IC2") (pin "8") (pinfunction "OUT_8") (pintype "output"))
      (node (ref "R6") (pin "2") (pinfunction "2_2") (pintype "passive"))
    )
    (net (code "66") (name "Net-(IC3A--IN)") (class "Default")
      (node (ref "C20") (pin "2") (pinfunction "2_2") (pintype "passive"))
      (node (ref "IC3") (pin "2") (pinfunction "-IN_2") (pintype "input"))
      (node (ref "R15") (pin "1") (pinfunction "1_1") (pintype "passive"))
    )
    (net (code "67") (name "Net-(IC3A-OUT)") (class "Default")
      (node (ref "C19") (pin "1") (pinfunction "1_1") (pintype "passive"))
      (node (ref "IC3") (pin "1") (pinfunction "OUT_1") (pintype "output"))
      (node (ref "R15") (pin "2") (pinfunction "2_2") (pintype "passive"))
      (node (ref "R16") (pin "1") (pinfunction "1_1") (pintype "passive"))
    )
    (net (code "68") (name "Net-(IC3B--IN)") (class "Default")
      (node (ref "C22") (pin "2") (pinfunction "2_2") (pintype "passive"))
      (node (ref "IC3") (pin "6") (pinfunction "-IN_6") (pintype "input"))
      (node (ref "R18") (pin "1") (pinfunction "1_1") (pintype "passive"))
    )
    (net (code "69") (name "Net-(IC3B-OUT)") (class "Default")
      (node (ref "C21") (pin "1") (pinfunction "1_1") (pintype "passive"))
      (node (ref "IC3") (pin "7") (pinfunction "OUT_7") (pintype "output"))
      (node (ref "R18") (pin "2") (pinfunction "2_2") (pintype "passive"))
      (node (ref "R19") (pin "1") (pinfunction "1_1") (pintype "passive"))
    )
    (net (code "70") (name "Net-(IC3C--IN)") (class "Default")
      (node (ref "IC3") (pin "9") (pinfunction "-IN_9") (pintype "input"))
      (node (ref "R19") (pin "2") (pinfunction "2_2") (pintype "passive"))
      (node (ref "R25") (pin "1") (pinfunction "1_1") (pintype "passive"))
    )
    (net (code "71") (name "Net-(IC3C-OUT)") (class "Default")
      (node (ref "IC3") (pin "12") (pinfunction "+IN_12") (pintype "input"))
      (node (ref "IC3") (pin "8") (pinfunction "OUT_8") (pintype "output"))
      (node (ref "R25") (pin "2") (pinfunction "2_2") (pintype "passive"))
    )
    (net (code "72") (name "Net-(IC4A--IN)") (class "Default")
      (node (ref "C24") (pin "2") (pinfunction "2_2") (pintype "passive"))
      (node (ref "IC4") (pin "2") (pinfunction "-IN_2") (pintype "input"))
      (node (ref "R40") (pin "1") (pinfunction "1_1") (pintype "passive"))
    )
    (net (code "73") (name "Net-(IC4A-OUT)") (class "Default")
      (node (ref "C23") (pin "1") (pinfunction "1_1") (pintype "passive"))
      (node (ref "IC4") (pin "1") (pinfunction "OUT_1") (pintype "output"))
      (node (ref "R36") (pin "1") (pinfunction "1_1") (pintype "passive"))
      (node (ref "R40") (pin "2") (pinfunction "2_2") (pintype "passive"))
    )
    (net (code "74") (name "Net-(IC4B--IN)") (class "Default")
      (node (ref "C26") (pin "2") (pinfunction "2_2") (pintype "passive"))
      (node (ref "IC4") (pin "6") (pinfunction "-IN_6") (pintype "input"))
      (node (ref "R38") (pin "1") (pinfunction "1_1") (pintype "passive"))
    )
    (net (code "75") (name "Net-(IC4B-OUT)") (class "Default")
      (node (ref "C25") (pin "1") (pinfunction "1_1") (pintype "passive"))
      (node (ref "IC4") (pin "7") (pinfunction "OUT_7") (pintype "output"))
      (node (ref "R38") (pin "2") (pinfunction "2_2") (pintype "passive"))
      (node (ref "R41") (pin "1") (pinfunction "1_1") (pintype "passive"))
    )
    (net (code "76") (name "Net-(IC4C--IN)") (class "Default")
      (node (ref "IC4") (pin "9") (pinfunction "-IN_9") (pintype "input"))
      (node (ref "R41") (pin "2") (pinfunction "2_2") (pintype "passive"))
      (node (ref "R42") (pin "1") (pinfunction "1_1") (pintype "passive"))
    )
    (net (code "77") (name "Net-(IC4C-OUT)") (class "Default")
      (node (ref "IC4") (pin "12") (pinfunction "+IN_12") (pintype "input"))
      (node (ref "IC4") (pin "8") (pinfunction "OUT_8") (pintype "output"))
      (node (ref "R42") (pin "2") (pinfunction "2_2") (pintype "passive"))
    )
    (net (code "78") (name "Net-(IC5A-+IN)") (class "Default")
      (node (ref "C38") (pin "1") (pinfunction "1_1") (pintype "passive"))
      (node (ref "IC5") (pin "3") (pinfunction "+IN_3") (pintype "input"))
      (node (ref "R39") (pin "1") (pinfunction "1_1") (pintype "passive"))
    )
    (net (code "79") (name "Net-(IC5A--IN)") (class "Default")
      (node (ref "IC5") (pin "1") (pinfunction "OUT_1") (pintype "output"))
      (node (ref "IC5") (pin "2") (pinfunction "-IN_2") (pintype "input"))
      (node (ref "R30") (pin "1") (pinfunction "1_1") (pintype "passive"))
    )
    (net (code "80") (name "Net-(IC5B--IN)") (class "Default")
      (node (ref "IC5") (pin "6") (pinfunction "-IN_6") (pintype "input"))
      (node (ref "R23") (pin "1") (pinfunction "1_1") (pintype "passive"))
      (node (ref "R30") (pin "2") (pinfunction "2_2") (pintype "passive"))
    )
    (net (code "81") (name "Net-(IC5B-OUT)") (class "Default")
      (node (ref "C31") (pin "1") (pinfunction "1_1") (pintype "passive"))
      (node (ref "IC5") (pin "7") (pinfunction "OUT_7") (pintype "output"))
      (node (ref "R1") (pin "1") (pinfunction "1_1") (pintype "passive"))
      (node (ref "R13") (pin "1") (pinfunction "1_1") (pintype "passive"))
      (node (ref "R23") (pin "2") (pinfunction "2_2") (pintype "passive"))
      (node (ref "R33") (pin "1") (pinfunction "1_1") (pintype "passive"))
      (node (ref "R7") (pin "1") (pinfunction "1_1") (pintype "passive"))
    )
    (net (code "82") (name "Net-(IC7A-+IN)") (class "Default")
      (node (ref "C30") (pin "2") (pinfunction "2_2") (pintype "passive"))
      (node (ref "IC7") (pin "3") (pinfunction "+IN_3") (pintype "input"))
      (node (ref "R20") (pin "2") (pinfunction "2_2") (pintype "passive"))
    )
    (net (code "83") (name "Net-(IC7A--IN)") (class "Default")
      (node (ref "IC7") (pin "1") (pinfunction "OUT_1") (pintype "output"))
      (node (ref "IC7") (pin "2") (pinfunction "-IN_2") (pintype "input"))
      (node (ref "R21") (pin "1") (pinfunction "1_1") (pintype "passive"))
      (node (ref "R22") (pin "2") (pinfunction "2_2") (pintype "passive"))
    )
    (net (code "84") (name "Net-(IC7B--IN)") (class "Default")
      (node (ref "IC7") (pin "6") (pinfunction "-IN_6") (pintype "input"))
      (node (ref "R22") (pin "1") (pinfunction "1_1") (pintype "passive"))
      (node (ref "R24") (pin "1") (pinfunction "1_1") (pintype "passive"))
    )
    (net (code "85") (name "Net-(LD1-PadC)") (class "Default")
      (node (ref "LD1") (pin "C") (pinfunction "C_C") (pintype "passive"))
      (node (ref "R48") (pin "1") (pinfunction "1_1") (pintype "passive"))
    )
    (net (code "86") (name "Net-(LD2-PadC)") (class "Default")
      (node (ref "LD2") (pin "C") (pinfunction "C_C") (pintype "passive"))
      (node (ref "R47") (pin "1") (pinfunction "1_1") (pintype "passive"))
    )
    (net (code "87") (name "Net-(LD3-PadC)") (class "Default")
      (node (ref "LD3") (pin "C") (pinfunction "C_C") (pintype "passive"))
      (node (ref "R46") (pin "1") (pinfunction "1_1") (pintype "passive"))
    )
    (net (code "88") (name "Net-(LD4-PadC)") (class "Default")
      (node (ref "LD4") (pin "C") (pinfunction "C_C") (pintype "passive"))
      (node (ref "R45") (pin "1") (pinfunction "1_1") (pintype "passive"))
    )
    (net (code "89") (name "Net-(LD5-PadC)") (class "Default")
      (node (ref "LD5") (pin "C") (pinfunction "C_C") (pintype "passive"))
      (node (ref "R44") (pin "1") (pinfunction "1_1") (pintype "passive"))
    )
    (net (code "90") (name "Net-(LD6-PadC)") (class "Default")
      (node (ref "LD6") (pin "C") (pinfunction "C_C") (pintype "passive"))
      (node (ref "R43") (pin "1") (pinfunction "1_1") (pintype "passive"))
    )
    (net (code "91") (name "Net-(LD7-PadC)") (class "Default")
      (node (ref "LD7") (pin "C") (pinfunction "C_C") (pintype "passive"))
      (node (ref "R59") (pin "1") (pinfunction "1_1") (pintype "passive"))
    )
    (net (code "92") (name "Net-(LD8-PadC)") (class "Default")
      (node (ref "LD8") (pin "C") (pinfunction "C_C") (pintype "passive"))
      (node (ref "R58") (pin "1") (pinfunction "1_1") (pintype "passive"))
    )
    (net (code "93") (name "Net-(LD9-PadC)") (class "Default")
      (node (ref "LD9") (pin "C") (pinfunction "C_C") (pintype "passive"))
      (node (ref "R57") (pin "1") (pinfunction "1_1") (pintype "passive"))
    )
    (net (code "94") (name "Net-(LD10-PadC)") (class "Default")
      (node (ref "LD10") (pin "C") (pinfunction "C_C") (pintype "passive"))
      (node (ref "R56") (pin "1") (pinfunction "1_1") (pintype "passive"))
    )
    (net (code "95") (name "Net-(LD11-PadC)") (class "Default")
      (node (ref "LD11") (pin "C") (pinfunction "C_C") (pintype "passive"))
      (node (ref "R55") (pin "1") (pinfunction "1_1") (pintype "passive"))
    )
    (net (code "96") (name "Net-(LD12-PadC)") (class "Default")
      (node (ref "LD12") (pin "C") (pinfunction "C_C") (pintype "passive"))
      (node (ref "R60") (pin "1") (pinfunction "1_1") (pintype "passive"))
    )
    (net (code "97") (name "Net-(LD13-PadC)") (class "Default")
      (node (ref "LD13") (pin "C") (pinfunction "C_C") (pintype "passive"))
      (node (ref "R72") (pin "1") (pinfunction "1_1") (pintype "passive"))
    )
    (net (code "98") (name "Net-(LD14-PadC)") (class "Default")
      (node (ref "LD14") (pin "C") (pinfunction "C_C") (pintype "passive"))
      (node (ref "R71") (pin "1") (pinfunction "1_1") (pintype "passive"))
    )
    (net (code "99") (name "Net-(LD15-PadC)") (class "Default")
      (node (ref "LD15") (pin "C") (pinfunction "C_C") (pintype "passive"))
      (node (ref "R70") (pin "1") (pinfunction "1_1") (pintype "passive"))
    )
    (net (code "100") (name "Net-(LD16-PadC)") (class "Default")
      (node (ref "LD16") (pin "C") (pinfunction "C_C") (pintype "passive"))
      (node (ref "R69") (pin "1") (pinfunction "1_1") (pintype "passive"))
    )
    (net (code "101") (name "Net-(LD17-PadC)") (class "Default")
      (node (ref "LD17") (pin "C") (pinfunction "C_C") (pintype "passive"))
      (node (ref "R68") (pin "1") (pinfunction "1_1") (pintype "passive"))
    )
    (net (code "102") (name "Net-(LD18-PadC)") (class "Default")
      (node (ref "LD18") (pin "C") (pinfunction "C_C") (pintype "passive"))
      (node (ref "R67") (pin "1") (pinfunction "1_1") (pintype "passive"))
    )
    (net (code "103") (name "Net-(LD19-PadC)") (class "Default")
      (node (ref "LD19") (pin "C") (pinfunction "C_C") (pintype "passive"))
      (node (ref "R84") (pin "1") (pinfunction "1_1") (pintype "passive"))
    )
    (net (code "104") (name "Net-(LD20-PadC)") (class "Default")
      (node (ref "LD20") (pin "C") (pinfunction "C_C") (pintype "passive"))
      (node (ref "R83") (pin "1") (pinfunction "1_1") (pintype "passive"))
    )
    (net (code "105") (name "Net-(LD21-PadC)") (class "Default")
      (node (ref "LD21") (pin "C") (pinfunction "C_C") (pintype "passive"))
      (node (ref "R82") (pin "1") (pinfunction "1_1") (pintype "passive"))
    )
    (net (code "106") (name "Net-(LD22-PadC)") (class "Default")
      (node (ref "LD22") (pin "C") (pinfunction "C_C") (pintype "passive"))
      (node (ref "R81") (pin "1") (pinfunction "1_1") (pintype "passive"))
    )
    (net (code "107") (name "Net-(LD23-PadC)") (class "Default")
      (node (ref "LD23") (pin "C") (pinfunction "C_C") (pintype "passive"))
      (node (ref "R80") (pin "1") (pinfunction "1_1") (pintype "passive"))
    )
    (net (code "108") (name "Net-(LD24-PadC)") (class "Default")
      (node (ref "LD24") (pin "C") (pinfunction "C_C") (pintype "passive"))
      (node (ref "R79") (pin "1") (pinfunction "1_1") (pintype "passive"))
    )
    (net (code "109") (name "Net-(LD25-PadC)") (class "Default")
      (node (ref "LD25") (pin "C") (pinfunction "C_C") (pintype "passive"))
      (node (ref "R95") (pin "1") (pinfunction "1_1") (pintype "passive"))
    )
    (net (code "110") (name "Net-(LD26-PadC)") (class "Default")
      (node (ref "LD26") (pin "C") (pinfunction "C_C") (pintype "passive"))
      (node (ref "R94") (pin "1") (pinfunction "1_1") (pintype "passive"))
    )
    (net (code "111") (name "Net-(LD27-PadC)") (class "Default")
      (node (ref "LD27") (pin "C") (pinfunction "C_C") (pintype "passive"))
      (node (ref "R93") (pin "1") (pinfunction "1_1") (pintype "passive"))
    )
    (net (code "112") (name "Net-(LD28-PadC)") (class "Default")
      (node (ref "LD28") (pin "C") (pinfunction "C_C") (pintype "passive"))
      (node (ref "R92") (pin "1") (pinfunction "1_1") (pintype "passive"))
    )
    (net (code "113") (name "Net-(LD29-PadC)") (class "Default")
      (node (ref "LD29") (pin "C") (pinfunction "C_C") (pintype "passive"))
      (node (ref "R91") (pin "1") (pinfunction "1_1") (pintype "passive"))
    )
    (net (code "114") (name "Net-(LD30-PadC)") (class "Default")
      (node (ref "LD30") (pin "C") (pinfunction "C_C") (pintype "passive"))
      (node (ref "R96") (pin "1") (pinfunction "1_1") (pintype "passive"))
    )
    (net (code "115") (name "Net-(T1-B)") (class "Default")
      (node (ref "R54") (pin "1") (pinfunction "1_1") (pintype "passive"))
      (node (ref "T1") (pin "1") (pinfunction "B_1") (pintype "bidirectional"))
    )
    (net (code "116") (name "Net-(T1-C)") (class "Default")
      (node (ref "R48") (pin "2") (pinfunction "2_2") (pintype "passive"))
      (node (ref "T1") (pin "3") (pinfunction "C_3") (pintype "bidirectional"))
    )
    (net (code "117") (name "Net-(T2-B)") (class "Default")
      (node (ref "R53") (pin "1") (pinfunction "1_1") (pintype "passive"))
      (node (ref "T2") (pin "1") (pinfunction "B_1") (pintype "bidirectional"))
    )
    (net (code "118") (name "Net-(T2-C)") (class "Default")
      (node (ref "R47") (pin "2") (pinfunction "2_2") (pintype "passive"))
      (node (ref "T2") (pin "3") (pinfunction "C_3") (pintype "bidirectional"))
    )
    (net (code "119") (name "Net-(T3-B)") (class "Default")
      (node (ref "R52") (pin "1") (pinfunction "1_1") (pintype "passive"))
      (node (ref "T3") (pin "1") (pinfunction "B_1") (pintype "bidirectional"))
    )
    (net (code "120") (name "Net-(T3-C)") (class "Default")
      (node (ref "R46") (pin "2") (pinfunction "2_2") (pintype "passive"))
      (node (ref "T3") (pin "3") (pinfunction "C_3") (pintype "bidirectional"))
    )
    (net (code "121") (name "Net-(T4-B)") (class "Default")
      (node (ref "R51") (pin "1") (pinfunction "1_1") (pintype "passive"))
      (node (ref "T4") (pin "1") (pinfunction "B_1") (pintype "bidirectional"))
    )
    (net (code "122") (name "Net-(T4-C)") (class "Default")
      (node (ref "R45") (pin "2") (pinfunction "2_2") (pintype "passive"))
      (node (ref "T4") (pin "3") (pinfunction "C_3") (pintype "bidirectional"))
    )
    (net (code "123") (name "Net-(T5-B)") (class "Default")
      (node (ref "R50") (pin "1") (pinfunction "1_1") (pintype "passive"))
      (node (ref "T5") (pin "1") (pinfunction "B_1") (pintype "bidirectional"))
    )
    (net (code "124") (name "Net-(T5-C)") (class "Default")
      (node (ref "R44") (pin "2") (pinfunction "2_2") (pintype "passive"))
      (node (ref "T5") (pin "3") (pinfunction "C_3") (pintype "bidirectional"))
    )
    (net (code "125") (name "Net-(T6-B)") (class "Default")
      (node (ref "R49") (pin "1") (pinfunction "1_1") (pintype "passive"))
      (node (ref "T6") (pin "1") (pinfunction "B_1") (pintype "bidirectional"))
    )
    (net (code "126") (name "Net-(T6-C)") (class "Default")
      (node (ref "R43") (pin "2") (pinfunction "2_2") (pintype "passive"))
      (node (ref "T6") (pin "3") (pinfunction "C_3") (pintype "bidirectional"))
    )
    (net (code "127") (name "Net-(T7-B)") (class "Default")
      (node (ref "R61") (pin "1") (pinfunction "1_1") (pintype "passive"))
      (node (ref "T7") (pin "1") (pinfunction "B_1") (pintype "bidirectional"))
    )
    (net (code "128") (name "Net-(T7-C)") (class "Default")
      (node (ref "R55") (pin "2") (pinfunction "2_2") (pintype "passive"))
      (node (ref "T7") (pin "3") (pinfunction "C_3") (pintype "bidirectional"))
    )
    (net (code "129") (name "Net-(T8-B)") (class "Default")
      (node (ref "R62") (pin "1") (pinfunction "1_1") (pintype "passive"))
      (node (ref "T8") (pin "1") (pinfunction "B_1") (pintype "bidirectional"))
    )
    (net (code "130") (name "Net-(T8-C)") (class "Default")
      (node (ref "R56") (pin "2") (pinfunction "2_2") (pintype "passive"))
      (node (ref "T8") (pin "3") (pinfunction "C_3") (pintype "bidirectional"))
    )
    (net (code "131") (name "Net-(T9-B)") (class "Default")
      (node (ref "R63") (pin "1") (pinfunction "1_1") (pintype "passive"))
      (node (ref "T9") (pin "1") (pinfunction "B_1") (pintype "bidirectional"))
    )
    (net (code "132") (name "Net-(T9-C)") (class "Default")
      (node (ref "R57") (pin "2") (pinfunction "2_2") (pintype "passive"))
      (node (ref "T9") (pin "3") (pinfunction "C_3") (pintype "bidirectional"))
    )
    (net (code "133") (name "Net-(T10-B)") (class "Default")
      (node (ref "R64") (pin "1") (pinfunction "1_1") (pintype "passive"))
      (node (ref "T10") (pin "1") (pinfunction "B_1") (pintype "bidirectional"))
    )
    (net (code "134") (name "Net-(T10-C)") (class "Default")
      (node (ref "R58") (pin "2") (pinfunction "2_2") (pintype "passive"))
      (node (ref "T10") (pin "3") (pinfunction "C_3") (pintype "bidirectional"))
    )
    (net (code "135") (name "Net-(T11-B)") (class "Default")
      (node (ref "R65") (pin "1") (pinfunction "1_1") (pintype "passive"))
      (node (ref "T11") (pin "1") (pinfunction "B_1") (pintype "bidirectional"))
    )
    (net (code "136") (name "Net-(T11-C)") (class "Default")
      (node (ref "R59") (pin "2") (pinfunction "2_2") (pintype "passive"))
      (node (ref "T11") (pin "3") (pinfunction "C_3") (pintype "bidirectional"))
    )
    (net (code "137") (name "Net-(T12-B)") (class "Default")
      (node (ref "R66") (pin "1") (pinfunction "1_1") (pintype "passive"))
      (node (ref "T12") (pin "1") (pinfunction "B_1") (pintype "bidirectional"))
    )
    (net (code "138") (name "Net-(T12-C)") (class "Default")
      (node (ref "R60") (pin "2") (pinfunction "2_2") (pintype "passive"))
      (node (ref "T12") (pin "3") (pinfunction "C_3") (pintype "bidirectional"))
    )
    (net (code "139") (name "Net-(T13-B)") (class "Default")
      (node (ref "R78") (pin "1") (pinfunction "1_1") (pintype "passive"))
      (node (ref "T13") (pin "1") (pinfunction "B_1") (pintype "bidirectional"))
    )
    (net (code "140") (name "Net-(T13-C)") (class "Default")
      (node (ref "R72") (pin "2") (pinfunction "2_2") (pintype "passive"))
      (node (ref "T13") (pin "3") (pinfunction "C_3") (pintype "bidirectional"))
    )
    (net (code "141") (name "Net-(T14-B)") (class "Default")
      (node (ref "R77") (pin "1") (pinfunction "1_1") (pintype "passive"))
      (node (ref "T14") (pin "1") (pinfunction "B_1") (pintype "bidirectional"))
    )
    (net (code "142") (name "Net-(T14-C)") (class "Default")
      (node (ref "R71") (pin "2") (pinfunction "2_2") (pintype "passive"))
      (node (ref "T14") (pin "3") (pinfunction "C_3") (pintype "bidirectional"))
    )
    (net (code "143") (name "Net-(T15-B)") (class "Default")
      (node (ref "R76") (pin "1") (pinfunction "1_1") (pintype "passive"))
      (node (ref "T15") (pin "1") (pinfunction "B_1") (pintype "bidirectional"))
    )
    (net (code "144") (name "Net-(T15-C)") (class "Default")
      (node (ref "R70") (pin "2") (pinfunction "2_2") (pintype "passive"))
      (node (ref "T15") (pin "3") (pinfunction "C_3") (pintype "bidirectional"))
    )
    (net (code "145") (name "Net-(T16-B)") (class "Default")
      (node (ref "R75") (pin "1") (pinfunction "1_1") (pintype "passive"))
      (node (ref "T16") (pin "1") (pinfunction "B_1") (pintype "bidirectional"))
    )
    (net (code "146") (name "Net-(T16-C)") (class "Default")
      (node (ref "R69") (pin "2") (pinfunction "2_2") (pintype "passive"))
      (node (ref "T16") (pin "3") (pinfunction "C_3") (pintype "bidirectional"))
    )
    (net (code "147") (name "Net-(T17-B)") (class "Default")
      (node (ref "R74") (pin "1") (pinfunction "1_1") (pintype "passive"))
      (node (ref "T17") (pin "1") (pinfunction "B_1") (pintype "bidirectional"))
    )
    (net (code "148") (name "Net-(T17-C)") (class "Default")
      (node (ref "R68") (pin "2") (pinfunction "2_2") (pintype "passive"))
      (node (ref "T17") (pin "3") (pinfunction "C_3") (pintype "bidirectional"))
    )
    (net (code "149") (name "Net-(T18-B)") (class "Default")
      (node (ref "R73") (pin "1") (pinfunction "1_1") (pintype "passive"))
      (node (ref "T18") (pin "1") (pinfunction "B_1") (pintype "bidirectional"))
    )
    (net (code "150") (name "Net-(T18-C)") (class "Default")
      (node (ref "R67") (pin "2") (pinfunction "2_2") (pintype "passive"))
      (node (ref "T18") (pin "3") (pinfunction "C_3") (pintype "bidirectional"))
    )
    (net (code "151") (name "Net-(T19-B)") (class "Default")
      (node (ref "R90") (pin "1") (pinfunction "1_1") (pintype "passive"))
      (node (ref "T19") (pin "1") (pinfunction "B_1") (pintype "bidirectional"))
    )
    (net (code "152") (name "Net-(T19-C)") (class "Default")
      (node (ref "R84") (pin "2") (pinfunction "2_2") (pintype "passive"))
      (node (ref "T19") (pin "3") (pinfunction "C_3") (pintype "bidirectional"))
    )
    (net (code "153") (name "Net-(T20-B)") (class "Default")
      (node (ref "R89") (pin "1") (pinfunction "1_1") (pintype "passive"))
      (node (ref "T20") (pin "1") (pinfunction "B_1") (pintype "bidirectional"))
    )
    (net (code "154") (name "Net-(T20-C)") (class "Default")
      (node (ref "R83") (pin "2") (pinfunction "2_2") (pintype "passive"))
      (node (ref "T20") (pin "3") (pinfunction "C_3") (pintype "bidirectional"))
    )
    (net (code "155") (name "Net-(T21-B)") (class "Default")
      (node (ref "R88") (pin "1") (pinfunction "1_1") (pintype "passive"))
      (node (ref "T21") (pin "1") (pinfunction "B_1") (pintype "bidirectional"))
    )
    (net (code "156") (name "Net-(T21-C)") (class "Default")
      (node (ref "R82") (pin "2") (pinfunction "2_2") (pintype "passive"))
      (node (ref "T21") (pin "3") (pinfunction "C_3") (pintype "bidirectional"))
    )
    (net (code "157") (name "Net-(T22-B)") (class "Default")
      (node (ref "R87") (pin "1") (pinfunction "1_1") (pintype "passive"))
      (node (ref "T22") (pin "1") (pinfunction "B_1") (pintype "bidirectional"))
    )
    (net (code "158") (name "Net-(T22-C)") (class "Default")
      (node (ref "R81") (pin "2") (pinfunction "2_2") (pintype "passive"))
      (node (ref "T22") (pin "3") (pinfunction "C_3") (pintype "bidirectional"))
    )
    (net (code "159") (name "Net-(T23-B)") (class "Default")
      (node (ref "R86") (pin "1") (pinfunction "1_1") (pintype "passive"))
      (node (ref "T23") (pin "1") (pinfunction "B_1") (pintype "bidirectional"))
    )
    (net (code "160") (name "Net-(T23-C)") (class "Default")
      (node (ref "R80") (pin "2") (pinfunction "2_2") (pintype "passive"))
      (node (ref "T23") (pin "3") (pinfunction "C_3") (pintype "bidirectional"))
    )
    (net (code "161") (name "Net-(T24-B)") (class "Default")
      (node (ref "R85") (pin "1") (pinfunction "1_1") (pintype "passive"))
      (node (ref "T24") (pin "1") (pinfunction "B_1") (pintype "bidirectional"))
    )
    (net (code "162") (name "Net-(T24-C)") (class "Default")
      (node (ref "R79") (pin "2") (pinfunction "2_2") (pintype "passive"))
      (node (ref "T24") (pin "3") (pinfunction "C_3") (pintype "bidirectional"))
    )
    (net (code "163") (name "Net-(T25-B)") (class "Default")
      (node (ref "R102") (pin "1") (pinfunction "1_1") (pintype "passive"))
      (node (ref "T25") (pin "1") (pinfunction "B_1") (pintype "bidirectional"))
    )
    (net (code "164") (name "Net-(T25-C)") (class "Default")
      (node (ref "R96") (pin "2") (pinfunction "2_2") (pintype "passive"))
      (node (ref "T25") (pin "3") (pinfunction "C_3") (pintype "bidirectional"))
    )
    (net (code "165") (name "Net-(T26-B)") (class "Default")
      (node (ref "R101") (pin "1") (pinfunction "1_1") (pintype "passive"))
      (node (ref "T26") (pin "1") (pinfunction "B_1") (pintype "bidirectional"))
    )
    (net (code "166") (name "Net-(T26-C)") (class "Default")
      (node (ref "R95") (pin "2") (pinfunction "2_2") (pintype "passive"))
      (node (ref "T26") (pin "3") (pinfunction "C_3") (pintype "bidirectional"))
    )
    (net (code "167") (name "Net-(T27-B)") (class "Default")
      (node (ref "R100") (pin "1") (pinfunction "1_1") (pintype "passive"))
      (node (ref "T27") (pin "1") (pinfunction "B_1") (pintype "bidirectional"))
    )
    (net (code "168") (name "Net-(T27-C)") (class "Default")
      (node (ref "R94") (pin "2") (pinfunction "2_2") (pintype "passive"))
      (node (ref "T27") (pin "3") (pinfunction "C_3") (pintype "bidirectional"))
    )
    (net (code "169") (name "Net-(T28-B)") (class "Default")
      (node (ref "R99") (pin "1") (pinfunction "1_1") (pintype "passive"))
      (node (ref "T28") (pin "1") (pinfunction "B_1") (pintype "bidirectional"))
    )
    (net (code "170") (name "Net-(T28-C)") (class "Default")
      (node (ref "R93") (pin "2") (pinfunction "2_2") (pintype "passive"))
      (node (ref "T28") (pin "3") (pinfunction "C_3") (pintype "bidirectional"))
    )
    (net (code "171") (name "Net-(T29-B)") (class "Default")
      (node (ref "R98") (pin "1") (pinfunction "1_1") (pintype "passive"))
      (node (ref "T29") (pin "1") (pinfunction "B_1") (pintype "bidirectional"))
    )
    (net (code "172") (name "Net-(T29-C)") (class "Default")
      (node (ref "R92") (pin "2") (pinfunction "2_2") (pintype "passive"))
      (node (ref "T29") (pin "3") (pinfunction "C_3") (pintype "bidirectional"))
    )
    (net (code "173") (name "Net-(T30-B)") (class "Default")
      (node (ref "R97") (pin "1") (pinfunction "1_1") (pintype "passive"))
      (node (ref "T30") (pin "1") (pinfunction "B_1") (pintype "bidirectional"))
    )
    (net (code "174") (name "Net-(T30-C)") (class "Default")
      (node (ref "R91") (pin "2") (pinfunction "2_2") (pintype "passive"))
      (node (ref "T30") (pin "3") (pinfunction "C_3") (pintype "bidirectional"))
    )
    (net (code "175") (name "Net-(U1-NFB)") (class "Default")
      (node (ref "CFF") (pin "2") (pinfunction "2_2") (pintype "passive"))
      (node (ref "RFB1") (pin "2") (pinfunction "2_2") (pintype "passive"))
      (node (ref "RFB2") (pin "1") (pinfunction "1_1") (pintype "passive"))
      (node (ref "U1") (pin "3") (pinfunction "NFB_3") (pintype "input"))
    )
    (net (code "176") (name "Net-(U1-SW)") (class "Default")
      (node (ref "CCUK") (pin "1") (pinfunction "1_1") (pintype "passive"))
      (node (ref "L2") (pin "2") (pinfunction "2_2") (pintype "passive"))
      (node (ref "U1") (pin "1") (pinfunction "SW_1") (pintype "output"))
    )
    (net (code "177") (name "Net-(U2-FB)") (class "Default")
      (node (ref "CF") (pin "2") (pinfunction "2_2") (pintype "passive"))
      (node (ref "R31") (pin "1") (pinfunction "1_1") (pintype "passive"))
      (node (ref "R35") (pin "1") (pinfunction "1_1") (pintype "passive"))
      (node (ref "U2") (pin "3") (pinfunction "FB_3") (pintype "input"))
    )
    (net (code "178") (name "Net-(U2-SHDN)") (class "Default")
      (node (ref "R32") (pin "1") (pinfunction "1_1") (pintype "passive"))
      (node (ref "U2") (pin "4") (pinfunction "SHDN_4") (pintype "input"))
    )
    (net (code "179") (name "PB5V") (class "Default")
      (node (ref "C40") (pin "2") (pinfunction "2_2") (pintype "passive"))
      (node (ref "C41") (pin "1") (pinfunction "1_1") (pintype "passive"))
      (node (ref "C42") (pin "1") (pinfunction "1_1") (pintype "passive"))
      (node (ref "C5") (pin "1") (pinfunction "1_1") (pintype "passive"))
      (node (ref "J2") (pin "2") (pinfunction "2_2") (pintype "passive"))
      (node (ref "L1") (pin "1") (pinfunction "1_1") (pintype "passive"))
      (node (ref "R104") (pin "2") (pinfunction "2_2") (pintype "passive"))
      (node (ref "R26") (pin "1") (pinfunction "1_1") (pintype "passive"))
      (node (ref "R26") (pin "2") (pinfunction "2_2") (pintype "passive"))
      (node (ref "R32") (pin "2") (pinfunction "2_2") (pintype "passive"))
      (node (ref "U2") (pin "5") (pinfunction "VIN_5") (pintype "input"))
    )
    (net (code "180") (name "TP_OUT") (class "Default")
      (node (ref "D100") (pin "2") (pinfunction "A_2") (pintype "passive"))
      (node (ref "IC1") (pin "7") (pinfunction "OUT_7") (pintype "output"))
      (node (ref "R12") (pin "2") (pinfunction "2_2") (pintype "passive"))
    )
    (net (code "181") (name "V+") (class "Default")
      (node (ref "C27") (pin "1") (pinfunction "1_1") (pintype "passive"))
      (node (ref "C28") (pin "1") (pinfunction "1_1") (pintype "passive"))
      (node (ref "C29") (pin "1") (pinfunction "1_1") (pintype "passive"))
      (node (ref "C32") (pin "1") (pinfunction "1_1") (pintype "passive"))
      (node (ref "C39") (pin "1") (pinfunction "1_1") (pintype "passive"))
      (node (ref "C9") (pin "1") (pinfunction "1_1") (pintype "passive"))
      (node (ref "IC1") (pin "8") (pinfunction "V+_8") (pintype "power_in"))
      (node (ref "IC2") (pin "4") (pinfunction "V+_4") (pintype "power_in"))
      (node (ref "IC3") (pin "4") (pinfunction "V+_4") (pintype "power_in"))
      (node (ref "IC4") (pin "4") (pinfunction "V+_4") (pintype "power_in"))
      (node (ref "IC5") (pin "8") (pinfunction "V+_8") (pintype "power_in"))
      (node (ref "IC7") (pin "8") (pinfunction "V+_8") (pintype "power_in"))
      (node (ref "LD1") (pin "A") (pinfunction "A_A") (pintype "passive"))
      (node (ref "LD10") (pin "A") (pinfunction "A_A") (pintype "passive"))
      (node (ref "LD11") (pin "A") (pinfunction "A_A") (pintype "passive"))
      (node (ref "LD12") (pin "A") (pinfunction "A_A") (pintype "passive"))
      (node (ref "LD13") (pin "A") (pinfunction "A_A") (pintype "passive"))
      (node (ref "LD14") (pin "A") (pinfunction "A_A") (pintype "passive"))
      (node (ref "LD15") (pin "A") (pinfunction "A_A") (pintype "passive"))
      (node (ref "LD16") (pin "A") (pinfunction "A_A") (pintype "passive"))
      (node (ref "LD17") (pin "A") (pinfunction "A_A") (pintype "passive"))
      (node (ref "LD18") (pin "A") (pinfunction "A_A") (pintype "passive"))
      (node (ref "LD19") (pin "A") (pinfunction "A_A") (pintype "passive"))
      (node (ref "LD2") (pin "A") (pinfunction "A_A") (pintype "passive"))
      (node (ref "LD20") (pin "A") (pinfunction "A_A") (pintype "passive"))
      (node (ref "LD21") (pin "A") (pinfunction "A_A") (pintype "passive"))
      (node (ref "LD22") (pin "A") (pinfunction "A_A") (pintype "passive"))
      (node (ref "LD23") (pin "A") (pinfunction "A_A") (pintype "passive"))
      (node (ref "LD24") (pin "A") (pinfunction "A_A") (pintype "passive"))
      (node (ref "LD25") (pin "A") (pinfunction "A_A") (pintype "passive"))
      (node (ref "LD26") (pin "A") (pinfunction "A_A") (pintype "passive"))
      (node (ref "LD27") (pin "A") (pinfunction "A_A") (pintype "passive"))
      (node (ref "LD28") (pin "A") (pinfunction "A_A") (pintype "passive"))
      (node (ref "LD29") (pin "A") (pinfunction "A_A") (pintype "passive"))
      (node (ref "LD3") (pin "A") (pinfunction "A_A") (pintype "passive"))
      (node (ref "LD30") (pin "A") (pinfunction "A_A") (pintype "passive"))
      (node (ref "LD4") (pin "A") (pinfunction "A_A") (pintype "passive"))
      (node (ref "LD5") (pin "A") (pinfunction "A_A") (pintype "passive"))
      (node (ref "LD6") (pin "A") (pinfunction "A_A") (pintype "passive"))
      (node (ref "LD7") (pin "A") (pinfunction "A_A") (pintype "passive"))
      (node (ref "LD8") (pin "A") (pinfunction "A_A") (pintype "passive"))
      (node (ref "LD9") (pin "A") (pinfunction "A_A") (pintype "passive"))
      (node (ref "R104") (pin "1") (pinfunction "1_1") (pintype "passive"))
      (node (ref "R27") (pin "2") (pinfunction "2_2") (pintype "passive"))
    )
    (net (code "182") (name "V-") (class "Default")
      (node (ref "C10") (pin "2") (pinfunction "2_2") (pintype "passive"))
      (node (ref "C11") (pin "2") (pinfunction "2_2") (pintype "passive"))
      (node (ref "C12") (pin "2") (pinfunction "2_2") (pintype "passive"))
      (node (ref "C13") (pin "2") (pinfunction "2_2") (pintype "passive"))
      (node (ref "C4") (pin "2") (pinfunction "2_2") (pintype "passive"))
      (node (ref "C8") (pin "2") (pinfunction "2_2") (pintype "passive"))
      (node (ref "IC1") (pin "4") (pinfunction "V-_4") (pintype "power_in"))
      (node (ref "IC2") (pin "11") (pinfunction "V-_11") (pintype "power_in"))
      (node (ref "IC3") (pin "11") (pinfunction "V-_11") (pintype "power_in"))
      (node (ref "IC4") (pin "11") (pinfunction "V-_11") (pintype "power_in"))
      (node (ref "IC5") (pin "4") (pinfunction "V-_4") (pintype "power_in"))
      (node (ref "IC7") (pin "4") (pinfunction "V-_4") (pintype "power_in"))
      (node (ref "R103") (pin "2") (pinfunction "2_2") (pintype "passive"))
      (node (ref "R105") (pin "2") (pinfunction "2_2") (pintype "passive"))
    )
  )
)
